# P1R4.net
KiCad netlist of a schematic drawn in EAGLE
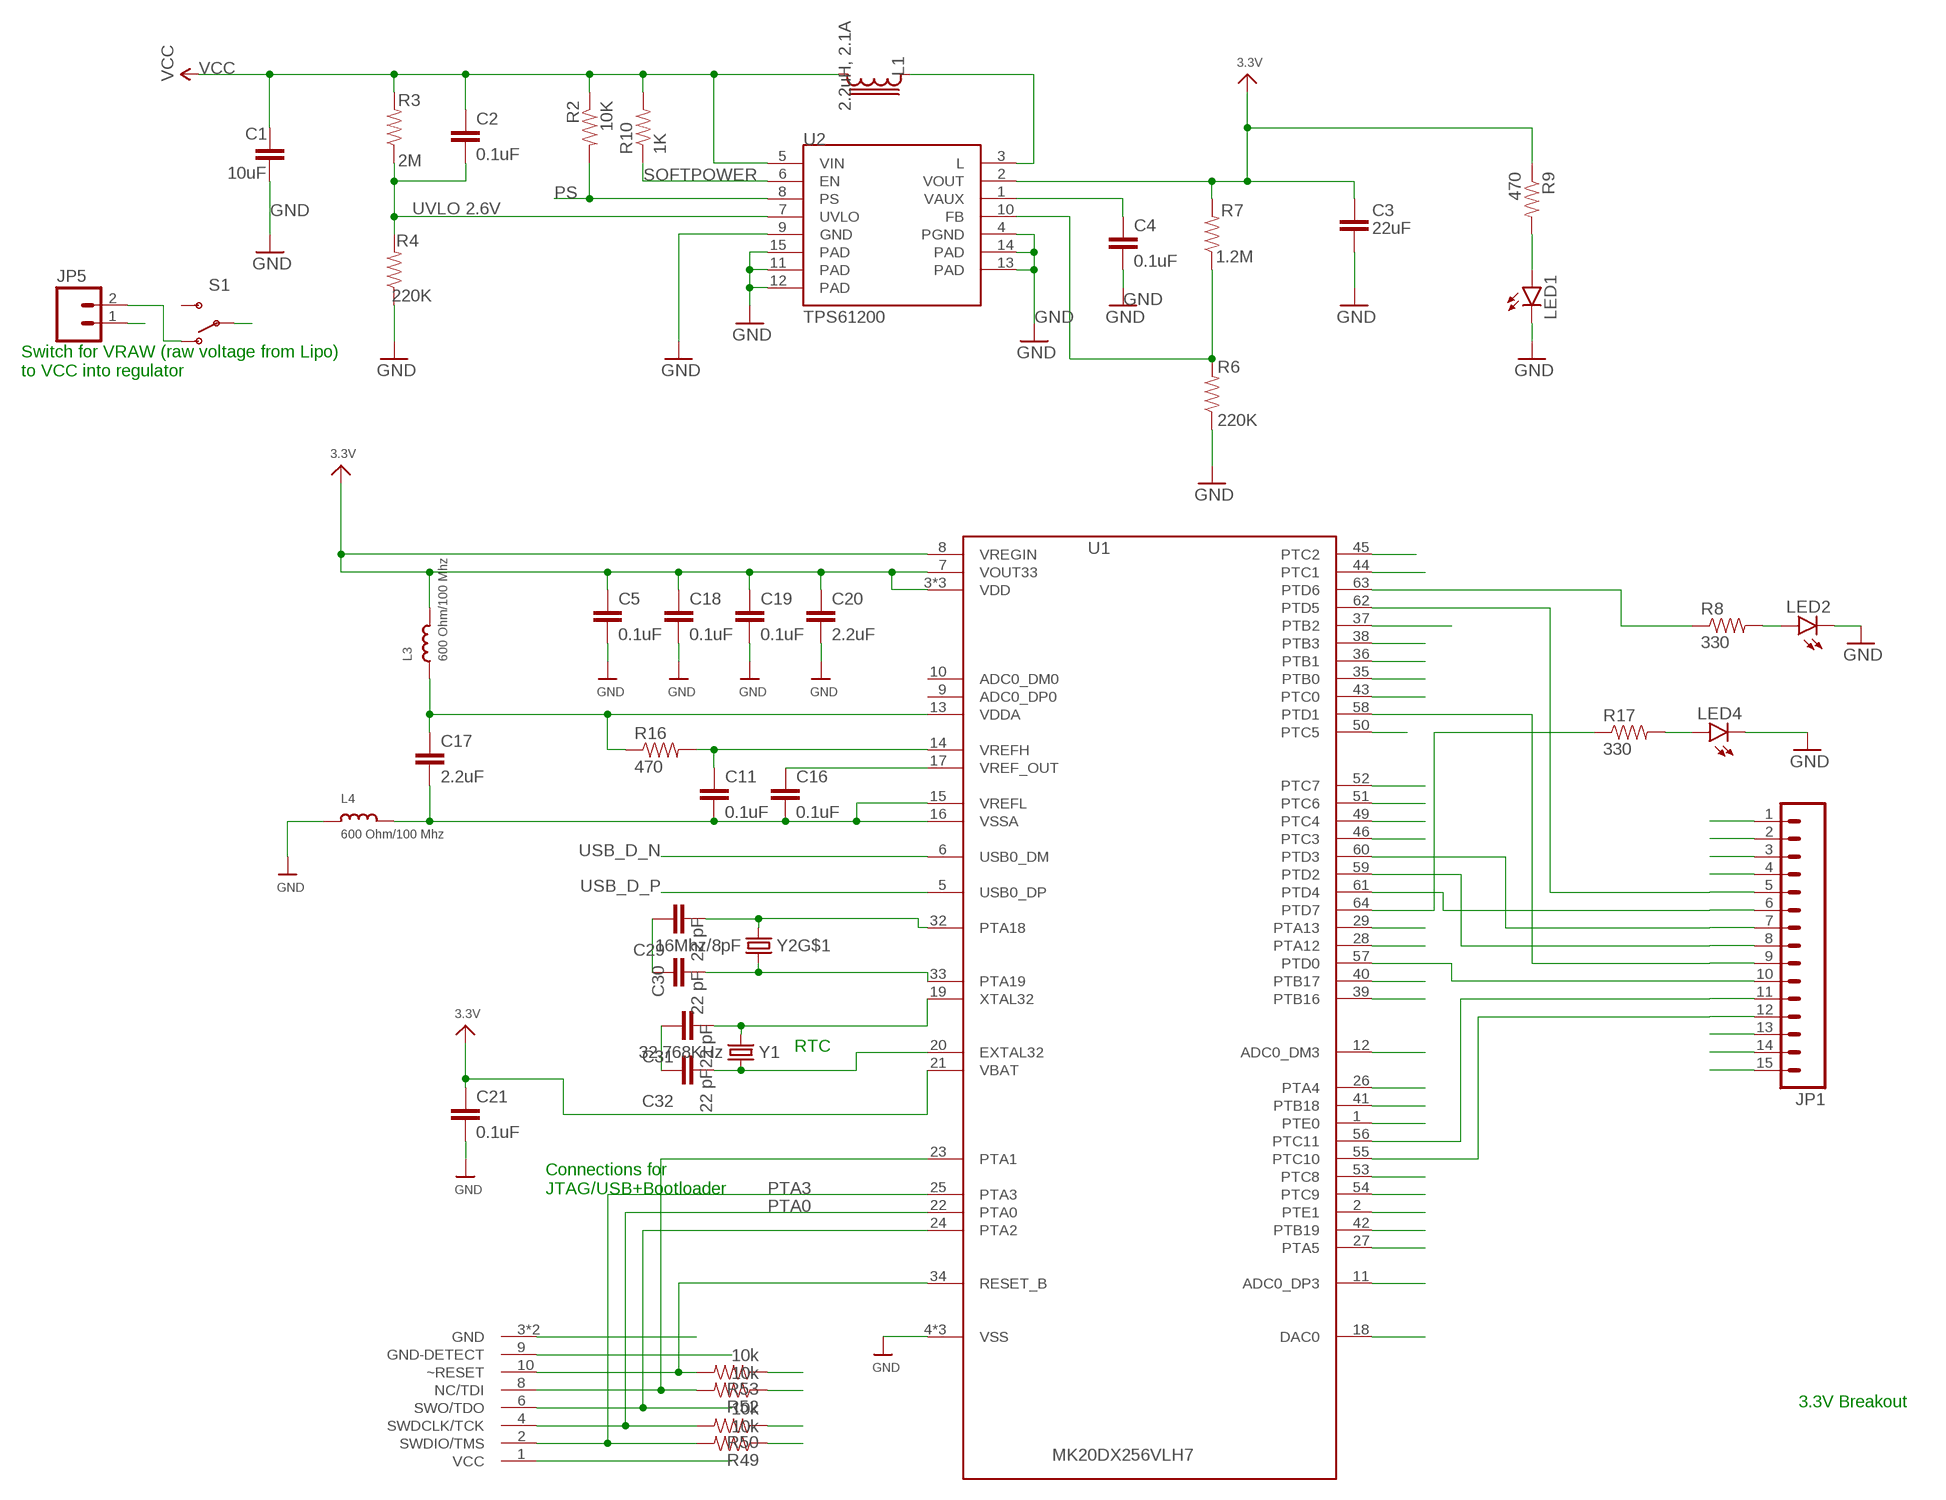
[diagram p0: schematic, sheet 1]
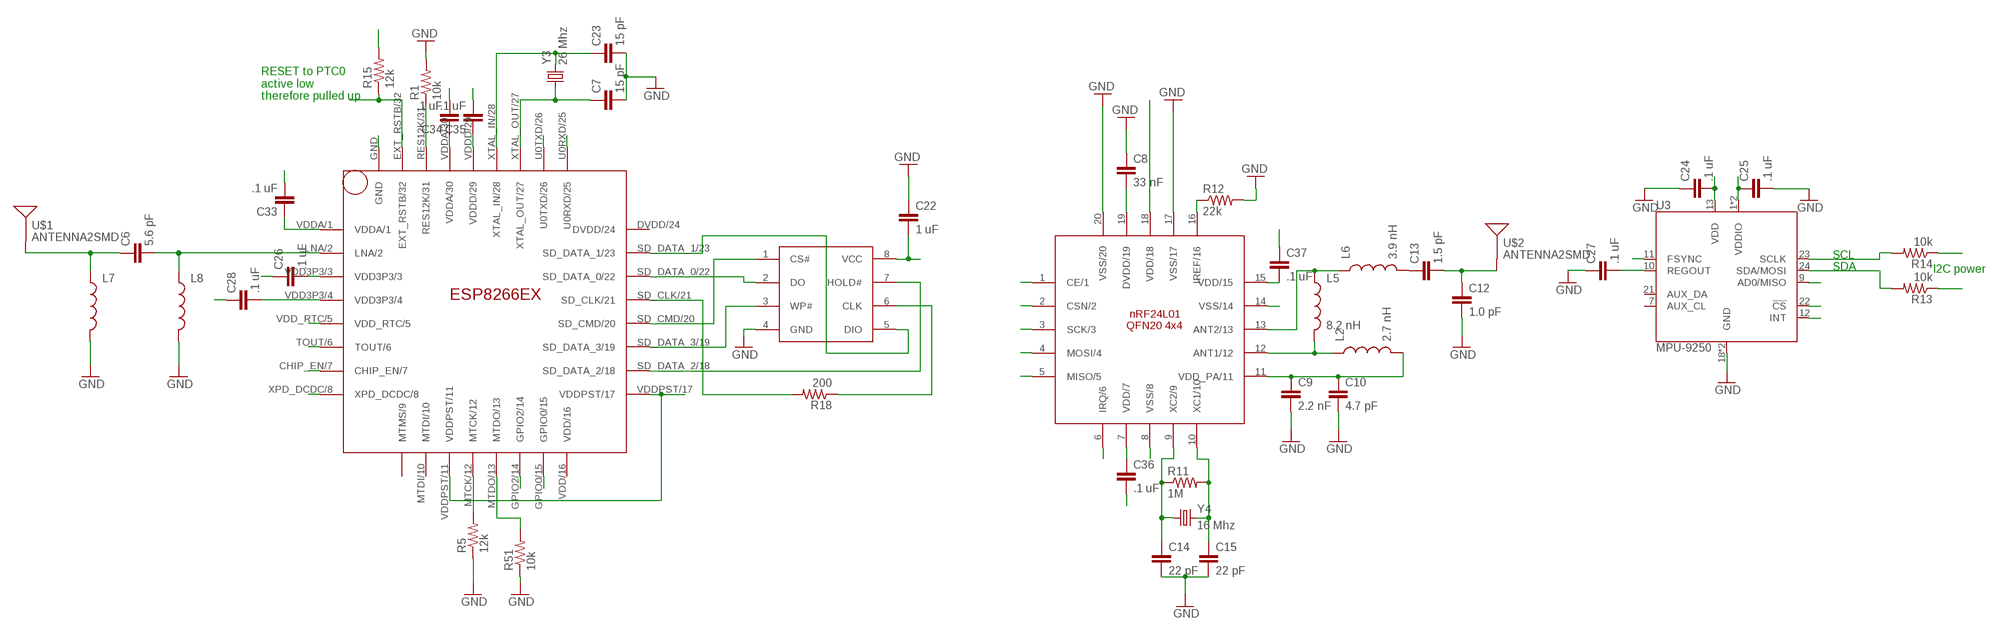
[diagram p1: schematic, sheet 2]
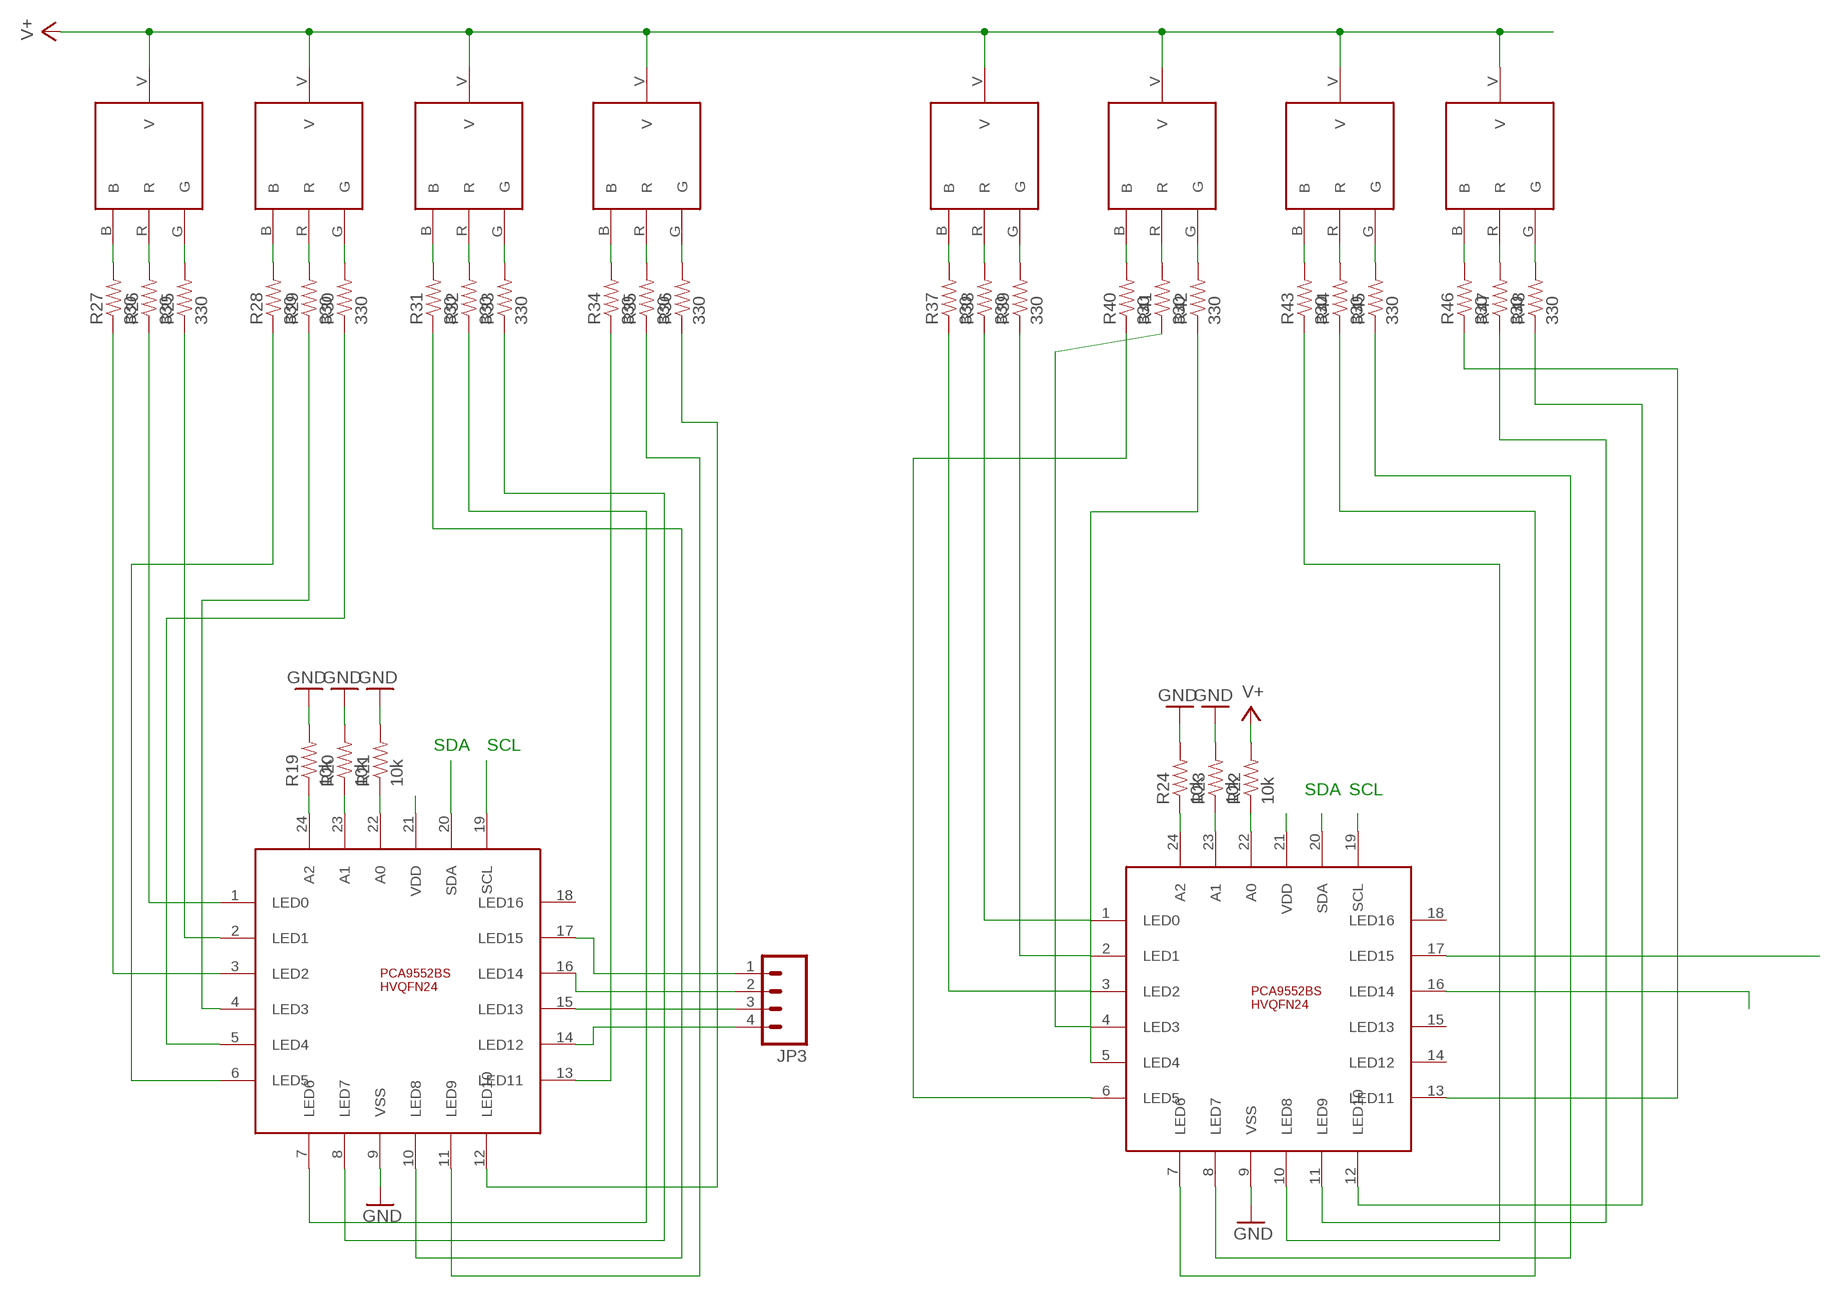
[diagram p2: schematic, sheet 3]

(export (version "E")
  (design (tool "Eeschema 10.0.6"))
  (components
    (comp (ref "JP3")
      (value "M04PTH")
      (footprint "eagle-import:1X04")
      (libsource (lib "eagle-import") (part "M04PTH"))
    )
    (comp (ref "R19")
      (value "10k")
      (footprint "eagle-import:0603-RES")
      (libsource (lib "eagle-import") (part "RESISTOR0603-RES"))
    )
    (comp (ref "R20")
      (value "10k")
      (footprint "eagle-import:0603-RES")
      (libsource (lib "eagle-import") (part "RESISTOR0603-RES"))
    )
    (comp (ref "R21")
      (value "10k")
      (footprint "eagle-import:0603-RES")
      (libsource (lib "eagle-import") (part "RESISTOR0603-RES"))
    )
    (comp (ref "R22")
      (value "10k")
      (footprint "eagle-import:0603-RES")
      (libsource (lib "eagle-import") (part "RESISTOR0603-RES"))
    )
    (comp (ref "R23")
      (value "10k")
      (footprint "eagle-import:0603-RES")
      (libsource (lib "eagle-import") (part "RESISTOR0603-RES"))
    )
    (comp (ref "R24")
      (value "10k")
      (footprint "eagle-import:0603-RES")
      (libsource (lib "eagle-import") (part "RESISTOR0603-RES"))
    )
    (comp (ref "R25")
      (value "330")
      (footprint "eagle-import:0402-RES")
      (libsource (lib "eagle-import") (part "RESISTOR0402-RES"))
    )
    (comp (ref "R26")
      (value "330")
      (footprint "eagle-import:0402-RES")
      (libsource (lib "eagle-import") (part "RESISTOR0402-RES"))
    )
    (comp (ref "R27")
      (value "330")
      (footprint "eagle-import:0402-RES")
      (libsource (lib "eagle-import") (part "RESISTOR0402-RES"))
    )
    (comp (ref "R28")
      (value "330")
      (footprint "eagle-import:0402-RES")
      (libsource (lib "eagle-import") (part "RESISTOR0402-RES"))
    )
    (comp (ref "R29")
      (value "330")
      (footprint "eagle-import:0402-RES")
      (libsource (lib "eagle-import") (part "RESISTOR0402-RES"))
    )
    (comp (ref "R30")
      (value "330")
      (footprint "eagle-import:0402-RES")
      (libsource (lib "eagle-import") (part "RESISTOR0402-RES"))
    )
    (comp (ref "R31")
      (value "330")
      (footprint "eagle-import:0402-RES")
      (libsource (lib "eagle-import") (part "RESISTOR0402-RES"))
    )
    (comp (ref "R32")
      (value "330")
      (footprint "eagle-import:0402-RES")
      (libsource (lib "eagle-import") (part "RESISTOR0402-RES"))
    )
    (comp (ref "R33")
      (value "330")
      (footprint "eagle-import:0402-RES")
      (libsource (lib "eagle-import") (part "RESISTOR0402-RES"))
    )
    (comp (ref "R34")
      (value "330")
      (footprint "eagle-import:0402-RES")
      (libsource (lib "eagle-import") (part "RESISTOR0402-RES"))
    )
    (comp (ref "R35")
      (value "330")
      (footprint "eagle-import:0402-RES")
      (libsource (lib "eagle-import") (part "RESISTOR0402-RES"))
    )
    (comp (ref "R36")
      (value "330")
      (footprint "eagle-import:0402-RES")
      (libsource (lib "eagle-import") (part "RESISTOR0402-RES"))
    )
    (comp (ref "R37")
      (value "330")
      (footprint "eagle-import:0402-RES")
      (libsource (lib "eagle-import") (part "RESISTOR0402-RES"))
    )
    (comp (ref "R38")
      (value "330")
      (footprint "eagle-import:0402-RES")
      (libsource (lib "eagle-import") (part "RESISTOR0402-RES"))
    )
    (comp (ref "R39")
      (value "330")
      (footprint "eagle-import:0402-RES")
      (libsource (lib "eagle-import") (part "RESISTOR0402-RES"))
    )
    (comp (ref "R40")
      (value "330")
      (footprint "eagle-import:0402-RES")
      (libsource (lib "eagle-import") (part "RESISTOR0402-RES"))
    )
    (comp (ref "R41")
      (value "330")
      (footprint "eagle-import:0402-RES")
      (libsource (lib "eagle-import") (part "RESISTOR0402-RES"))
    )
    (comp (ref "R42")
      (value "330")
      (footprint "eagle-import:0402-RES")
      (libsource (lib "eagle-import") (part "RESISTOR0402-RES"))
    )
    (comp (ref "R43")
      (value "330")
      (footprint "eagle-import:0402-RES")
      (libsource (lib "eagle-import") (part "RESISTOR0402-RES"))
    )
    (comp (ref "R44")
      (value "330")
      (footprint "eagle-import:0402-RES")
      (libsource (lib "eagle-import") (part "RESISTOR0402-RES"))
    )
    (comp (ref "R45")
      (value "330")
      (footprint "eagle-import:0402-RES")
      (libsource (lib "eagle-import") (part "RESISTOR0402-RES"))
    )
    (comp (ref "R46")
      (value "330")
      (footprint "eagle-import:0402-RES")
      (libsource (lib "eagle-import") (part "RESISTOR0402-RES"))
    )
    (comp (ref "R47")
      (value "330")
      (footprint "eagle-import:0402-RES")
      (libsource (lib "eagle-import") (part "RESISTOR0402-RES"))
    )
    (comp (ref "R48")
      (value "330")
      (footprint "eagle-import:0402-RES")
      (libsource (lib "eagle-import") (part "RESISTOR0402-RES"))
    )
    (comp (ref "U$8")
      (value "LTST-C19FD1WT")
      (footprint "eagle-import:LTST-C19FD1WT")
      (libsource (lib "eagle-import") (part "LTST-C19FD1WT"))
    )
    (comp (ref "U$11")
      (value "LTST-C19FD1WT")
      (footprint "eagle-import:LTST-C19FD1WT")
      (libsource (lib "eagle-import") (part "LTST-C19FD1WT"))
    )
    (comp (ref "U$13")
      (value "LTST-C19FD1WT")
      (footprint "eagle-import:LTST-C19FD1WT")
      (libsource (lib "eagle-import") (part "LTST-C19FD1WT"))
    )
    (comp (ref "U$14")
      (value "LTST-C19FD1WT")
      (footprint "eagle-import:LTST-C19FD1WT")
      (libsource (lib "eagle-import") (part "LTST-C19FD1WT"))
    )
    (comp (ref "U$15")
      (value "LTST-C19FD1WT")
      (footprint "eagle-import:LTST-C19FD1WT")
      (libsource (lib "eagle-import") (part "LTST-C19FD1WT"))
    )
    (comp (ref "U$16")
      (value "LTST-C19FD1WT")
      (footprint "eagle-import:LTST-C19FD1WT")
      (libsource (lib "eagle-import") (part "LTST-C19FD1WT"))
    )
    (comp (ref "U$17")
      (value "LTST-C19FD1WT")
      (footprint "eagle-import:LTST-C19FD1WT")
      (libsource (lib "eagle-import") (part "LTST-C19FD1WT"))
    )
    (comp (ref "U$18")
      (value "LTST-C19FD1WT")
      (footprint "eagle-import:LTST-C19FD1WT")
      (libsource (lib "eagle-import") (part "LTST-C19FD1WT"))
    )
    (comp (ref "U$20")
      (value "PCA9552BS")
      (footprint "eagle-import:HVQFN24")
      (libsource (lib "eagle-import") (part "PCA9552BS"))
    )
    (comp (ref "U$21")
      (value "PCA9552BS")
      (footprint "eagle-import:HVQFN24")
      (libsource (lib "eagle-import") (part "PCA9552BS"))
    )
    (comp (ref "C1")
      (value "10uF")
      (footprint "eagle-import:0603-CAP")
      (fields (field (name "MF") "Murata") (field (name "MPN") "GRM188R60J106ME47D"))
      (libsource (lib "eagle-import") (part "CAPACITOR-10UF"))
    )
    (comp (ref "C2")
      (value "0.1uF")
      (footprint "eagle-import:0603-CAP")
      (fields (field (name "MF") "Kemet") (field (name "MPN") "C0603C104J3RACTU"))
      (libsource (lib "eagle-import") (part "CAPACITOR-0.1UF"))
    )
    (comp (ref "C3")
      (value "22uF")
      (footprint "eagle-import:0603-CAP")
      (fields (field (name "MF") "Murata") (field (name "MPN") "GRM188R60J226MEA0D"))
      (libsource (lib "eagle-import") (part "CAPACITOR-22UF"))
    )
    (comp (ref "C4")
      (value "0.1uF")
      (footprint "eagle-import:0603-CAP")
      (fields (field (name "MF") "Kemet") (field (name "MPN") "C0603C104J3RACTU"))
      (libsource (lib "eagle-import") (part "CAPACITOR-0.1UF"))
    )
    (comp (ref "C5")
      (value "0.1uF")
      (footprint "eagle-import:0603-CAP")
      (fields (field (name "MF") "Kemet") (field (name "MPN") "C0603C104J3RACTU"))
      (libsource (lib "eagle-import") (part "CAPACITOR-0.1UF"))
    )
    (comp (ref "C11")
      (value "0.1uF")
      (footprint "eagle-import:0603-CAP")
      (fields (field (name "MF") "Kemet") (field (name "MPN") "C0603C104J3RACTU"))
      (libsource (lib "eagle-import") (part "CAPACITOR-0.1UF"))
    )
    (comp (ref "C16")
      (value "0.1uF")
      (footprint "eagle-import:0603-CAP")
      (fields (field (name "MF") "Kemet") (field (name "MPN") "C0603C104J3RACTU"))
      (libsource (lib "eagle-import") (part "CAPACITOR-0.1UF"))
    )
    (comp (ref "C17")
      (value "2.2uF")
      (footprint "eagle-import:0603-CAP")
      (fields (field (name "MF") "Kemet") (field (name "MPN") "C0603C225K4PACTU"))
      (libsource (lib "eagle-import") (part "CAPACITOR-2.2UF"))
    )
    (comp (ref "C18")
      (value "0.1uF")
      (footprint "eagle-import:0603-CAP")
      (fields (field (name "MF") "Kemet") (field (name "MPN") "C0603C104J3RACTU"))
      (libsource (lib "eagle-import") (part "CAPACITOR-0.1UF"))
    )
    (comp (ref "C19")
      (value "0.1uF")
      (footprint "eagle-import:0603-CAP")
      (fields (field (name "MF") "Kemet") (field (name "MPN") "C0603C104J3RACTU"))
      (libsource (lib "eagle-import") (part "CAPACITOR-0.1UF"))
    )
    (comp (ref "C20")
      (value "2.2uF")
      (footprint "eagle-import:0603-CAP")
      (fields (field (name "MF") "Kemet") (field (name "MPN") "C0603C225K4PACTU"))
      (libsource (lib "eagle-import") (part "CAPACITOR-2.2UF"))
    )
    (comp (ref "C21")
      (value "0.1uF")
      (footprint "eagle-import:0603-CAP")
      (fields (field (name "MF") "Kemet") (field (name "MPN") "C0603C104J3RACTU"))
      (libsource (lib "eagle-import") (part "CAPACITOR-0.1UF"))
    )
    (comp (ref "C29")
      (value "22 pF")
      (footprint "eagle-import:0603-CAP")
      (fields (field (name "MF") "Murata") (field (name "MPN") "GRM188R60J106ME47D"))
      (libsource (lib "eagle-import") (part "CAPACITOR-10UF"))
    )
    (comp (ref "C30")
      (value "22 pF")
      (footprint "eagle-import:0603-CAP")
      (fields (field (name "MF") "Murata") (field (name "MPN") "GRM188R60J106ME47D"))
      (libsource (lib "eagle-import") (part "CAPACITOR-10UF"))
    )
    (comp (ref "C31")
      (value "22 pF")
      (footprint "eagle-import:0603-CAP")
      (fields (field (name "MF") "Murata") (field (name "MPN") "GRM188R60J106ME47D"))
      (libsource (lib "eagle-import") (part "CAPACITOR-10UF"))
    )
    (comp (ref "C32")
      (value "22 pF")
      (footprint "eagle-import:0603-CAP")
      (fields (field (name "MF") "Murata") (field (name "MPN") "GRM188R60J106ME47D"))
      (libsource (lib "eagle-import") (part "CAPACITOR-10UF"))
    )
    (comp (ref "JP1")
      (value "M15")
      (footprint "eagle-import:1X15")
      (libsource (lib "eagle-import") (part "M15"))
    )
    (comp (ref "JP5")
      (value "M02PTH")
      (footprint "eagle-import:1X02")
      (libsource (lib "eagle-import") (part "M02PTH"))
    )
    (comp (ref "L1")
      (value "2.2uH, 2.1A")
      (footprint "eagle-import:LPS3015")
      (fields (field (name "MF") "Coilcraft") (field (name "MPN") "LPS3015-222MRB"))
      (libsource (lib "eagle-import") (part "LPS30152.2UH"))
    )
    (comp (ref "L3")
      (value "600 Ohm/100 Mhz")
      (footprint "eagle-import:0805")
      (fields (field (name "MF") "Taiyo Yuden") (field (name "MPN") "BK2125HM601-T"))
      (libsource (lib "eagle-import") (part "INDUCTOR-BK2125HM601-T"))
    )
    (comp (ref "L4")
      (value "600 Ohm/100 Mhz")
      (footprint "eagle-import:0805")
      (fields (field (name "MF") "Taiyo Yuden") (field (name "MPN") "BK2125HM601-T"))
      (libsource (lib "eagle-import") (part "INDUCTOR-BK2125HM601-T"))
    )
    (comp (ref "LED1")
      (value "LED-GREEN")
      (footprint "eagle-import:LED-0603")
      (fields (field (name "MF") "Avago") (field (name "MPN") "HSMG-C190"))
      (libsource (lib "eagle-import") (part "LED-GREEN"))
    )
    (comp (ref "LED2")
      (value "LED-GREEN")
      (footprint "eagle-import:LED-0603")
      (fields (field (name "MF") "Avago") (field (name "MPN") "HSMG-C190"))
      (libsource (lib "eagle-import") (part "LED-GREEN"))
    )
    (comp (ref "LED4")
      (value "LED-GREEN")
      (footprint "eagle-import:LED-0603")
      (fields (field (name "MF") "Avago") (field (name "MPN") "HSMG-C190"))
      (libsource (lib "eagle-import") (part "LED-GREEN"))
    )
    (comp (ref "R2")
      (value "10K")
      (footprint "eagle-import:0603-RES")
      (fields (field (name "MF") "Panasonic") (field (name "MPN") "ERJ-3GEYJ103V"))
      (libsource (lib "eagle-import") (part "RESISTOR-10K"))
    )
    (comp (ref "R3")
      (value "2M")
      (footprint "eagle-import:0603-RES")
      (fields (field (name "MF") "Panasonic") (field (name "MPN") "ERJ-3GEYJ205V"))
      (libsource (lib "eagle-import") (part "RESISTOR-2M"))
    )
    (comp (ref "R4")
      (value "220K")
      (footprint "eagle-import:0603-RES")
      (fields (field (name "MF") "Panasonic") (field (name "MPN") "ERJ-3GEYJ224V"))
      (libsource (lib "eagle-import") (part "RESISTOR-220K"))
    )
    (comp (ref "R6")
      (value "220K")
      (footprint "eagle-import:0603-RES")
      (fields (field (name "MF") "Panasonic") (field (name "MPN") "ERJ-3GEYJ224V"))
      (libsource (lib "eagle-import") (part "RESISTOR-220K"))
    )
    (comp (ref "R7")
      (value "1.2M")
      (footprint "eagle-import:0603-RES")
      (fields (field (name "MF") "Panasonic") (field (name "MPN") "ERJ-3GEYJ125V"))
      (libsource (lib "eagle-import") (part "RESISTOR-1.2M"))
    )
    (comp (ref "R8")
      (value "330")
      (footprint "eagle-import:0603-RES")
      (fields (field (name "MF") "Panasonic") (field (name "MPN") "ERJ-3GEYJ471V"))
      (libsource (lib "eagle-import") (part "RESISTOR-470"))
    )
    (comp (ref "R9")
      (value "470")
      (footprint "eagle-import:0603-RES")
      (fields (field (name "MF") "Panasonic") (field (name "MPN") "ERJ-3GEYJ471V"))
      (libsource (lib "eagle-import") (part "RESISTOR-470"))
    )
    (comp (ref "R10")
      (value "1K")
      (footprint "eagle-import:0603-RES")
      (fields (field (name "MF") "Panasonic") (field (name "MPN") "ERJ-3GEYJ102V"))
      (libsource (lib "eagle-import") (part "RESISTOR-1K"))
    )
    (comp (ref "R16")
      (value "470")
      (footprint "eagle-import:0603-RES")
      (fields (field (name "MF") "Panasonic") (field (name "MPN") "ERJ-3GEYJ471V"))
      (libsource (lib "eagle-import") (part "RESISTOR-470"))
    )
    (comp (ref "R17")
      (value "330")
      (footprint "eagle-import:0603-RES")
      (fields (field (name "MF") "Panasonic") (field (name "MPN") "ERJ-3GEYJ471V"))
      (libsource (lib "eagle-import") (part "RESISTOR-470"))
    )
    (comp (ref "R49")
      (value "10k")
      (footprint "eagle-import:0402-RES")
      (libsource (lib "eagle-import") (part "RESISTOR0402-RES"))
    )
    (comp (ref "R50")
      (value "10k")
      (footprint "eagle-import:0402-RES")
      (libsource (lib "eagle-import") (part "RESISTOR0402-RES"))
    )
    (comp (ref "R52")
      (value "10k")
      (footprint "eagle-import:0402-RES")
      (libsource (lib "eagle-import") (part "RESISTOR0402-RES"))
    )
    (comp (ref "R53")
      (value "10k")
      (footprint "eagle-import:0402-RES")
      (libsource (lib "eagle-import") (part "RESISTOR0402-RES"))
    )
    (comp (ref "S1")
      (value "SWITCH-SPDT-SMD-A")
      (footprint "eagle-import:SWITCH-SPST-SMD-A")
      (libsource (lib "eagle-import") (part "SWITCH-SPDT-SMD-A"))
    )
    (comp (ref "U$7")
      (value "2X5_0.05\"_CORTEX_DEBUGTH_NOKEY_UNSHROUDED")
      (footprint "eagle-import:2X5_0.05__TH_NS")
      (libsource (lib "eagle-import") (part "2X5_0.05{dblquote}_CORTEX_DEBUGTH_NOKEY_UNSHROUDED"))
    )
    (comp (ref "U1")
      (value "MK20DX256VLH7")
      (footprint "eagle-import:MK20DX256VLH7")
      (fields (field (name "MF") "Freescale"))
      (libsource (lib "eagle-import") (part "MK20DX256VLH7"))
    )
    (comp (ref "U2")
      (value "TPS61200")
      (footprint "eagle-import:QFN-10_PAD")
      (fields (field (name "MF") "Texas Instruments") (field (name "MPN") "TPS61200DRCR"))
      (libsource (lib "eagle-import") (part "TPS61200"))
    )
    (comp (ref "Y1")
      (value "32.768KHz")
      (footprint "eagle-import:CRYSTAL-TXC-7A")
      (fields (field (name "MF") "Epson Timing") (field (name "MPN") "FC-255 32.7680K-A3"))
      (libsource (lib "eagle-import") (part "CRYSTAL/32.768KHZ/SMD-TXC_7A"))
    )
    (comp (ref "Y2")
      (value "16Mhz/8pF")
      (footprint "eagle-import:CRYSTAL-SMD-5X3")
      (fields (field (name "MF") "ECS") (field (name "MPN") "ECS-160-8-30B-CKM"))
      (libsource (lib "eagle-import") (part "CRYSTAL/SMD-5X3-GND16MHZ/8PF"))
    )
    (comp (ref "C6")
      (value "5.6 pF")
      (footprint "eagle-import:0603-CAP")
      (libsource (lib "eagle-import") (part "CAP0603-CAP"))
    )
    (comp (ref "C7")
      (value "15 pF")
      (footprint "eagle-import:0603-CAP")
      (libsource (lib "eagle-import") (part "CAP0603-CAP"))
    )
    (comp (ref "C8")
      (value "33 nF")
      (footprint "eagle-import:0603-CAP")
      (libsource (lib "eagle-import") (part "CAP0603-CAP"))
    )
    (comp (ref "C9")
      (value "2.2 nF")
      (footprint "eagle-import:0603-CAP")
      (libsource (lib "eagle-import") (part "CAP0603-CAP"))
    )
    (comp (ref "C10")
      (value "4.7 pF")
      (footprint "eagle-import:0603-CAP")
      (libsource (lib "eagle-import") (part "CAP0603-CAP"))
    )
    (comp (ref "C12")
      (value "1.0 pF")
      (footprint "eagle-import:0603-CAP")
      (libsource (lib "eagle-import") (part "CAP0603-CAP"))
    )
    (comp (ref "C13")
      (value "1.5 pF")
      (footprint "eagle-import:0603-CAP")
      (libsource (lib "eagle-import") (part "CAP0603-CAP"))
    )
    (comp (ref "C14")
      (value "22 pF")
      (footprint "eagle-import:0603-CAP")
      (libsource (lib "eagle-import") (part "CAP0603-CAP"))
    )
    (comp (ref "C15")
      (value "22 pF")
      (footprint "eagle-import:0603-CAP")
      (libsource (lib "eagle-import") (part "CAP0603-CAP"))
    )
    (comp (ref "C22")
      (value "1 uF")
      (footprint "eagle-import:0603-CAP")
      (libsource (lib "eagle-import") (part "CAP0603-CAP"))
    )
    (comp (ref "C23")
      (value "15 pF")
      (footprint "eagle-import:0603-CAP")
      (libsource (lib "eagle-import") (part "CAP0603-CAP"))
    )
    (comp (ref "C24")
      (value ".1 uF")
      (footprint "eagle-import:0603-CAP")
      (libsource (lib "eagle-import") (part "CAP0603-CAP"))
    )
    (comp (ref "C25")
      (value ".1 uF")
      (footprint "eagle-import:0603-CAP")
      (libsource (lib "eagle-import") (part "CAP0603-CAP"))
    )
    (comp (ref "C26")
      (value ".1 uF")
      (footprint "eagle-import:0603-CAP")
      (libsource (lib "eagle-import") (part "CAP0603-CAP"))
    )
    (comp (ref "C27")
      (value ".1 uF")
      (footprint "eagle-import:0603-CAP")
      (libsource (lib "eagle-import") (part "CAP0603-CAP"))
    )
    (comp (ref "C28")
      (value ".1 uF")
      (footprint "eagle-import:0603-CAP")
      (libsource (lib "eagle-import") (part "CAP0603-CAP"))
    )
    (comp (ref "C33")
      (value ".1 uF")
      (footprint "eagle-import:0603-CAP")
      (libsource (lib "eagle-import") (part "CAP0603-CAP"))
    )
    (comp (ref "C34")
      (value ".1 uF")
      (footprint "eagle-import:0603-CAP")
      (libsource (lib "eagle-import") (part "CAP0603-CAP"))
    )
    (comp (ref "C35")
      (value ".1 uF")
      (footprint "eagle-import:0603-CAP")
      (libsource (lib "eagle-import") (part "CAP0603-CAP"))
    )
    (comp (ref "C36")
      (value ".1 uF")
      (footprint "eagle-import:0603-CAP")
      (libsource (lib "eagle-import") (part "CAP0603-CAP"))
    )
    (comp (ref "C37")
      (value ".1 uF")
      (footprint "eagle-import:0603-CAP")
      (libsource (lib "eagle-import") (part "CAP0603-CAP"))
    )
    (comp (ref "L2")
      (value "2.7 nH")
      (footprint "eagle-import:C0402")
      (libsource (lib "eagle-import") (part "INDUCTOR0402"))
    )
    (comp (ref "L5")
      (value "8.2 nH")
      (footprint "eagle-import:C0402")
      (libsource (lib "eagle-import") (part "INDUCTOR0402"))
    )
    (comp (ref "L6")
      (value "3.9 nH")
      (footprint "eagle-import:C0402")
      (libsource (lib "eagle-import") (part "INDUCTOR0402"))
    )
    (comp (ref "L7")
      (value "INDUCTOR30OHM,1.8A")
      (footprint "eagle-import:0603")
      (libsource (lib "eagle-import") (part "INDUCTOR30OHM,1.8A"))
    )
    (comp (ref "L8")
      (value "INDUCTOR30OHM,1.8A")
      (footprint "eagle-import:0603")
      (libsource (lib "eagle-import") (part "INDUCTOR30OHM,1.8A"))
    )
    (comp (ref "R1")
      (value "10k")
      (footprint "eagle-import:0603-RES")
      (libsource (lib "eagle-import") (part "SparkFun-Resistors_RESISTOR0603-RES"))
    )
    (comp (ref "R5")
      (value "12k")
      (footprint "eagle-import:0603-RES")
      (libsource (lib "eagle-import") (part "SparkFun-Resistors_RESISTOR0603-RES"))
    )
    (comp (ref "R11")
      (value "1M")
      (footprint "eagle-import:0603-RES")
      (libsource (lib "eagle-import") (part "SparkFun-Resistors_RESISTOR0603-RES"))
    )
    (comp (ref "R12")
      (value "22k")
      (footprint "eagle-import:0603-RES")
      (libsource (lib "eagle-import") (part "SparkFun-Resistors_RESISTOR0603-RES"))
    )
    (comp (ref "R13")
      (value "10k")
      (footprint "eagle-import:0603-RES")
      (libsource (lib "eagle-import") (part "SparkFun-Resistors_RESISTOR0603-RES"))
    )
    (comp (ref "R14")
      (value "10k")
      (footprint "eagle-import:0603-RES")
      (libsource (lib "eagle-import") (part "SparkFun-Resistors_RESISTOR0603-RES"))
    )
    (comp (ref "R15")
      (value "12k")
      (footprint "eagle-import:0603-RES")
      (libsource (lib "eagle-import") (part "SparkFun-Resistors_RESISTOR0603-RES"))
    )
    (comp (ref "R18")
      (value "200")
      (footprint "eagle-import:0603-RES")
      (libsource (lib "eagle-import") (part "SparkFun-Resistors_RESISTOR0603-RES"))
    )
    (comp (ref "R51")
      (value "10k")
      (footprint "eagle-import:0603-RES")
      (libsource (lib "eagle-import") (part "SparkFun-Resistors_RESISTOR0603-RES"))
    )
    (comp (ref "U$1")
      (value "ANTENNA2SMD")
      (footprint "eagle-import:ANTENNA-CHIP2")
      (libsource (lib "eagle-import") (part "ANTENNA2SMD"))
    )
    (comp (ref "U$2")
      (value "ANTENNA2SMD")
      (footprint "eagle-import:ANTENNA-CHIP2")
      (libsource (lib "eagle-import") (part "ANTENNA2SMD"))
    )
    (comp (ref "U$3")
      (value "25Q40")
      (footprint "eagle-import:SOP8")
      (libsource (lib "eagle-import") (part "25Q40"))
    )
    (comp (ref "U$4")
      (value "NRF24L01")
      (footprint "eagle-import:QFN20(4X4)")
      (libsource (lib "eagle-import") (part "NRF24L01"))
    )
    (comp (ref "U$6")
      (value "ESP8266EX")
      (footprint "eagle-import:QFN32")
      (libsource (lib "eagle-import") (part "ESP8266EX"))
    )
    (comp (ref "U3")
      (value "MPU-9250")
      (footprint "eagle-import:QFN-24_3MM")
      (libsource (lib "eagle-import") (part "MPU-9250"))
    )
    (comp (ref "Y3")
      (value "26 Mhz")
      (footprint "eagle-import:CRYSTAL-SMD-5X3")
      (libsource (lib "eagle-import") (part "CRYSTAL5X3"))
    )
    (comp (ref "Y4")
      (value "16 Mhz")
      (footprint "eagle-import:CRYSTAL-SMD-5X3")
      (libsource (lib "eagle-import") (part "CRYSTAL5X3"))
    )
  )
  (nets
    (net (code "1") (name "3.3V") (class "Default")
      (node (ref "C18") (pin "1") (pinfunction "1_1") (pintype "passive"))
      (node (ref "C19") (pin "1") (pinfunction "1_1") (pintype "passive"))
      (node (ref "C20") (pin "1") (pinfunction "1_1") (pintype "passive"))
      (node (ref "C21") (pin "1") (pinfunction "1_1") (pintype "passive"))
      (node (ref "C22") (pin "2") (pinfunction "2_2") (pintype "passive"))
      (node (ref "C24") (pin "2") (pinfunction "2_2") (pintype "passive"))
      (node (ref "C25") (pin "1") (pinfunction "1_1") (pintype "passive"))
      (node (ref "C26") (pin "2") (pinfunction "2_2") (pintype "passive"))
      (node (ref "C28") (pin "2") (pinfunction "2_2") (pintype "passive"))
      (node (ref "C3") (pin "1") (pinfunction "1_1") (pintype "passive"))
      (node (ref "C33") (pin "1") (pinfunction "1_1") (pintype "passive"))
      (node (ref "C34") (pin "1") (pinfunction "1_1") (pintype "passive"))
      (node (ref "C35") (pin "1") (pinfunction "1_1") (pintype "passive"))
      (node (ref "C36") (pin "1") (pinfunction "1_1") (pintype "passive"))
      (node (ref "C37") (pin "2") (pinfunction "2_2") (pintype "passive"))
      (node (ref "C5") (pin "1") (pinfunction "1_1") (pintype "passive"))
      (node (ref "JP1") (pin "13") (pinfunction "13_13") (pintype "passive"))
      (node (ref "JP1") (pin "14") (pinfunction "14_14") (pintype "passive"))
      (node (ref "JP1") (pin "15") (pinfunction "15_15") (pintype "passive"))
      (node (ref "L3") (pin "2") (pinfunction "2_2") (pintype "passive"))
      (node (ref "R13") (pin "1") (pinfunction "1_1") (pintype "passive"))
      (node (ref "R14") (pin "1") (pinfunction "1_1") (pintype "passive"))
      (node (ref "R15") (pin "2") (pinfunction "2_2") (pintype "passive"))
      (node (ref "R22") (pin "2") (pinfunction "2_2") (pintype "passive"))
      (node (ref "R49") (pin "1") (pinfunction "1_1") (pintype "passive"))
      (node (ref "R52") (pin "1") (pinfunction "1_1") (pintype "passive"))
      (node (ref "R53") (pin "1") (pinfunction "1_1") (pintype "passive"))
      (node (ref "R7") (pin "2") (pinfunction "2_2") (pintype "passive"))
      (node (ref "R9") (pin "1") (pinfunction "1_1") (pintype "passive"))
      (node (ref "U$11") (pin "V") (pinfunction "V_V") (pintype "bidirectional"))
      (node (ref "U$13") (pin "V") (pinfunction "V_V") (pintype "bidirectional"))
      (node (ref "U$14") (pin "V") (pinfunction "V_V") (pintype "bidirectional"))
      (node (ref "U$15") (pin "V") (pinfunction "V_V") (pintype "bidirectional"))
      (node (ref "U$16") (pin "V") (pinfunction "V_V") (pintype "bidirectional"))
      (node (ref "U$17") (pin "V") (pinfunction "V_V") (pintype "bidirectional"))
      (node (ref "U$18") (pin "V") (pinfunction "V_V") (pintype "bidirectional"))
      (node (ref "U$20") (pin "21") (pinfunction "VDD_21") (pintype "bidirectional"))
      (node (ref "U$21") (pin "21") (pinfunction "VDD_21") (pintype "bidirectional"))
      (node (ref "U$3") (pin "8") (pinfunction "VCC_8") (pintype "bidirectional"))
      (node (ref "U$4") (pin "15") (pinfunction "VDD/15_15") (pintype "bidirectional"))
      (node (ref "U$4") (pin "18") (pinfunction "VDD/18_18") (pintype "bidirectional"))
      (node (ref "U$4") (pin "7") (pinfunction "VDD/7_7") (pintype "bidirectional"))
      (node (ref "U$6") (pin "VDD3P3/3") (pinfunction "VDD3P3/3_VDD3P3/3") (pintype "bidirectional"))
      (node (ref "U$6") (pin "VDD3P3/4") (pinfunction "VDD3P3/4_VDD3P3/4") (pintype "bidirectional"))
      (node (ref "U$6") (pin "VDDA/1") (pinfunction "VDDA/1_VDDA/1") (pintype "bidirectional"))
      (node (ref "U$6") (pin "VDDA/30") (pinfunction "VDDA/30_VDDA/30") (pintype "bidirectional"))
      (node (ref "U$6") (pin "VDDD/29") (pinfunction "VDDD/29_VDDD/29") (pintype "bidirectional"))
      (node (ref "U$6") (pin "VDDPST/11") (pinfunction "VDDPST/11_VDDPST/11") (pintype "bidirectional"))
      (node (ref "U$6") (pin "VDDPST/17") (pinfunction "VDDPST/17_VDDPST/17") (pintype "bidirectional"))
      (node (ref "U$7") (pin "1") (pinfunction "VCC_1") (pintype "bidirectional"))
      (node (ref "U$8") (pin "V") (pinfunction "V_V") (pintype "bidirectional"))
      (node (ref "U1") (pin "21") (pinfunction "VBAT_21") (pintype "bidirectional"))
      (node (ref "U1") (pin "3") (pinfunction "VDD_3") (pintype "bidirectional"))
      (node (ref "U1") (pin "30") (pinfunction "VDD_30") (pintype "bidirectional"))
      (node (ref "U1") (pin "48") (pinfunction "VDD_48") (pintype "bidirectional"))
      (node (ref "U1") (pin "7") (pinfunction "VOUT33_7") (pintype "bidirectional"))
      (node (ref "U1") (pin "8") (pinfunction "VREGIN_8") (pintype "bidirectional"))
      (node (ref "U2") (pin "2") (pinfunction "VOUT_2") (pintype "passive"))
      (node (ref "U3") (pin "1") (pinfunction "VDDIO_1") (pintype "bidirectional"))
      (node (ref "U3") (pin "13") (pinfunction "VDD_13") (pintype "bidirectional"))
      (node (ref "U3") (pin "22") (pinfunction "~{CS}_22") (pintype "bidirectional"))
      (node (ref "U3") (pin "8") (pinfunction "VDDIO_8") (pintype "bidirectional"))
    )
    (net (code "2") (name "AD0") (class "Default")
      (node (ref "U1") (pin "45") (pinfunction "PTC2_45") (pintype "bidirectional"))
      (node (ref "U3") (pin "9") (pinfunction "AD0/MISO_9") (pintype "bidirectional"))
    )
    (net (code "3") (name "GND") (class "Default")
      (node (ref "C1") (pin "2") (pinfunction "2_2") (pintype "passive"))
      (node (ref "C10") (pin "2") (pinfunction "2_2") (pintype "passive"))
      (node (ref "C12") (pin "2") (pinfunction "2_2") (pintype "passive"))
      (node (ref "C14") (pin "2") (pinfunction "2_2") (pintype "passive"))
      (node (ref "C15") (pin "2") (pinfunction "2_2") (pintype "passive"))
      (node (ref "C18") (pin "2") (pinfunction "2_2") (pintype "passive"))
      (node (ref "C19") (pin "2") (pinfunction "2_2") (pintype "passive"))
      (node (ref "C20") (pin "2") (pinfunction "2_2") (pintype "passive"))
      (node (ref "C21") (pin "2") (pinfunction "2_2") (pintype "passive"))
      (node (ref "C22") (pin "1") (pinfunction "1_1") (pintype "passive"))
      (node (ref "C23") (pin "2") (pinfunction "2_2") (pintype "passive"))
      (node (ref "C24") (pin "1") (pinfunction "1_1") (pintype "passive"))
      (node (ref "C25") (pin "2") (pinfunction "2_2") (pintype "passive"))
      (node (ref "C26") (pin "1") (pinfunction "1_1") (pintype "passive"))
      (node (ref "C27") (pin "1") (pinfunction "1_1") (pintype "passive"))
      (node (ref "C28") (pin "1") (pinfunction "1_1") (pintype "passive"))
      (node (ref "C29") (pin "1") (pinfunction "1_1") (pintype "passive"))
      (node (ref "C3") (pin "2") (pinfunction "2_2") (pintype "passive"))
      (node (ref "C30") (pin "1") (pinfunction "1_1") (pintype "passive"))
      (node (ref "C31") (pin "1") (pinfunction "1_1") (pintype "passive"))
      (node (ref "C32") (pin "1") (pinfunction "1_1") (pintype "passive"))
      (node (ref "C33") (pin "2") (pinfunction "2_2") (pintype "passive"))
      (node (ref "C34") (pin "2") (pinfunction "2_2") (pintype "passive"))
      (node (ref "C35") (pin "2") (pinfunction "2_2") (pintype "passive"))
      (node (ref "C36") (pin "2") (pinfunction "2_2") (pintype "passive"))
      (node (ref "C37") (pin "1") (pinfunction "1_1") (pintype "passive"))
      (node (ref "C4") (pin "2") (pinfunction "2_2") (pintype "passive"))
      (node (ref "C5") (pin "2") (pinfunction "2_2") (pintype "passive"))
      (node (ref "C7") (pin "2") (pinfunction "2_2") (pintype "passive"))
      (node (ref "C8") (pin "1") (pinfunction "1_1") (pintype "passive"))
      (node (ref "C9") (pin "2") (pinfunction "2_2") (pintype "passive"))
      (node (ref "JP1") (pin "1") (pinfunction "1_1") (pintype "passive"))
      (node (ref "JP1") (pin "2") (pinfunction "2_2") (pintype "passive"))
      (node (ref "JP1") (pin "3") (pinfunction "3_3") (pintype "passive"))
      (node (ref "JP1") (pin "4") (pinfunction "4_4") (pintype "passive"))
      (node (ref "JP5") (pin "1") (pinfunction "1_1") (pintype "passive"))
      (node (ref "L4") (pin "1") (pinfunction "1_1") (pintype "passive"))
      (node (ref "L7") (pin "2") (pinfunction "2_2") (pintype "passive"))
      (node (ref "L8") (pin "2") (pinfunction "2_2") (pintype "passive"))
      (node (ref "LED1") (pin "C") (pinfunction "C_C") (pintype "passive"))
      (node (ref "LED2") (pin "C") (pinfunction "C_C") (pintype "passive"))
      (node (ref "LED4") (pin "C") (pinfunction "C_C") (pintype "passive"))
      (node (ref "R1") (pin "2") (pinfunction "2_2") (pintype "passive"))
      (node (ref "R12") (pin "2") (pinfunction "2_2") (pintype "passive"))
      (node (ref "R19") (pin "2") (pinfunction "2_2") (pintype "passive"))
      (node (ref "R20") (pin "2") (pinfunction "2_2") (pintype "passive"))
      (node (ref "R21") (pin "2") (pinfunction "2_2") (pintype "passive"))
      (node (ref "R23") (pin "2") (pinfunction "2_2") (pintype "passive"))
      (node (ref "R24") (pin "2") (pinfunction "2_2") (pintype "passive"))
      (node (ref "R4") (pin "1") (pinfunction "1_1") (pintype "passive"))
      (node (ref "R5") (pin "1") (pinfunction "1_1") (pintype "passive"))
      (node (ref "R50") (pin "1") (pinfunction "1_1") (pintype "passive"))
      (node (ref "R51") (pin "1") (pinfunction "1_1") (pintype "passive"))
      (node (ref "R6") (pin "1") (pinfunction "1_1") (pintype "passive"))
      (node (ref "U$20") (pin "9") (pinfunction "VSS_9") (pintype "bidirectional"))
      (node (ref "U$21") (pin "9") (pinfunction "VSS_9") (pintype "bidirectional"))
      (node (ref "U$3") (pin "4") (pinfunction "GND_4") (pintype "bidirectional"))
      (node (ref "U$4") (pin "14") (pinfunction "VSS/14_14") (pintype "bidirectional"))
      (node (ref "U$4") (pin "17") (pinfunction "VSS/17_17") (pintype "bidirectional"))
      (node (ref "U$4") (pin "20") (pinfunction "VSS/20_20") (pintype "bidirectional"))
      (node (ref "U$4") (pin "8") (pinfunction "VSS/8_8") (pintype "bidirectional"))
      (node (ref "U$6") (pin "GND") (pinfunction "GND_GND") (pintype "bidirectional"))
      (node (ref "U$7") (pin "3") (pinfunction "GND_3") (pintype "bidirectional"))
      (node (ref "U$7") (pin "5") (pinfunction "GND_5") (pintype "bidirectional"))
      (node (ref "U$7") (pin "9") (pinfunction "GND-DETECT_9") (pintype "bidirectional"))
      (node (ref "U1") (pin "31") (pinfunction "VSS_31") (pintype "bidirectional"))
      (node (ref "U1") (pin "4") (pinfunction "VSS_4") (pintype "bidirectional"))
      (node (ref "U1") (pin "47") (pinfunction "VSS_47") (pintype "bidirectional"))
      (node (ref "U2") (pin "11") (pinfunction "PAD_11") (pintype "power_in"))
      (node (ref "U2") (pin "12") (pinfunction "PAD_12") (pintype "power_in"))
      (node (ref "U2") (pin "13") (pinfunction "PAD_13") (pintype "power_in"))
      (node (ref "U2") (pin "14") (pinfunction "PAD_14") (pintype "power_in"))
      (node (ref "U2") (pin "15") (pinfunction "PAD_15") (pintype "power_in"))
      (node (ref "U2") (pin "4") (pinfunction "PGND_4") (pintype "power_in"))
      (node (ref "U2") (pin "9") (pinfunction "GND_9") (pintype "power_in"))
      (node (ref "U3") (pin "18") (pinfunction "GND_18") (pintype "bidirectional"))
      (node (ref "U3") (pin "20") (pinfunction "GND_20") (pintype "bidirectional"))
    )
    (net (code "4") (name "Net-(C6-Pad2)") (class "Default")
      (node (ref "C6") (pin "2") (pinfunction "2_2") (pintype "passive"))
      (node (ref "L8") (pin "1") (pinfunction "1_1") (pintype "passive"))
      (node (ref "U$6") (pin "LNA/2") (pinfunction "LNA/2_LNA/2") (pintype "bidirectional"))
    )
    (net (code "5") (name "Net-(C7-Pad1)") (class "Default")
      (node (ref "C7") (pin "1") (pinfunction "1_1") (pintype "passive"))
      (node (ref "U$6") (pin "XTAL_OUT/27") (pinfunction "XTAL_OUT/27_XTAL_OUT/27") (pintype "bidirectional"))
      (node (ref "Y3") (pin "1") (pinfunction "1_1") (pintype "passive"))
    )
    (net (code "6") (name "Net-(C13-Pad1)") (class "Default")
      (node (ref "C13") (pin "1") (pinfunction "1_1") (pintype "passive"))
      (node (ref "L6") (pin "2") (pinfunction "2_2") (pintype "passive"))
    )
    (net (code "7") (name "Net-(LED1-PadA)") (class "Default")
      (node (ref "LED1") (pin "A") (pinfunction "A_A") (pintype "passive"))
      (node (ref "R9") (pin "2") (pinfunction "2_2") (pintype "passive"))
    )
    (net (code "8") (name "Net-(LED2-PadA)") (class "Default")
      (node (ref "LED2") (pin "A") (pinfunction "A_A") (pintype "passive"))
      (node (ref "R8") (pin "2") (pinfunction "2_2") (pintype "passive"))
    )
    (net (code "9") (name "Net-(LED4-PadA)") (class "Default")
      (node (ref "LED4") (pin "A") (pinfunction "A_A") (pintype "passive"))
      (node (ref "R17") (pin "2") (pinfunction "2_2") (pintype "passive"))
    )
    (net (code "10") (name "Net-(R1-Pad1)") (class "Default")
      (node (ref "R1") (pin "1") (pinfunction "1_1") (pintype "passive"))
      (node (ref "U$6") (pin "RES12K/31") (pinfunction "RES12K/31_RES12K/31") (pintype "bidirectional"))
    )
    (net (code "11") (name "Net-(R5-Pad2)") (class "Default")
      (node (ref "R5") (pin "2") (pinfunction "2_2") (pintype "passive"))
      (node (ref "U$6") (pin "MTCK/12") (pinfunction "MTCK/12_MTCK/12") (pintype "bidirectional"))
    )
    (net (code "12") (name "Net-(R18-Pad2)") (class "Default")
      (node (ref "R18") (pin "2") (pinfunction "2_2") (pintype "passive"))
      (node (ref "U$6") (pin "SD_CLK/21") (pinfunction "SD_CLK/21_SD_CLK/21") (pintype "bidirectional"))
    )
    (net (code "13") (name "Net-(R25-Pad2)") (class "Default")
      (node (ref "R25") (pin "2") (pinfunction "2_2") (pintype "passive"))
      (node (ref "U$8") (pin "G") (pinfunction "G_G") (pintype "bidirectional"))
    )
    (net (code "14") (name "Net-(R26-Pad2)") (class "Default")
      (node (ref "R26") (pin "2") (pinfunction "2_2") (pintype "passive"))
      (node (ref "U$8") (pin "R") (pinfunction "R_R") (pintype "bidirectional"))
    )
    (net (code "15") (name "Net-(R27-Pad2)") (class "Default")
      (node (ref "R27") (pin "2") (pinfunction "2_2") (pintype "passive"))
      (node (ref "U$8") (pin "B") (pinfunction "B_B") (pintype "bidirectional"))
    )
    (net (code "16") (name "Net-(R28-Pad2)") (class "Default")
      (node (ref "R28") (pin "2") (pinfunction "2_2") (pintype "passive"))
      (node (ref "U$11") (pin "B") (pinfunction "B_B") (pintype "bidirectional"))
    )
    (net (code "17") (name "Net-(R29-Pad2)") (class "Default")
      (node (ref "R29") (pin "2") (pinfunction "2_2") (pintype "passive"))
      (node (ref "U$11") (pin "R") (pinfunction "R_R") (pintype "bidirectional"))
    )
    (net (code "18") (name "Net-(R30-Pad2)") (class "Default")
      (node (ref "R30") (pin "2") (pinfunction "2_2") (pintype "passive"))
      (node (ref "U$11") (pin "G") (pinfunction "G_G") (pintype "bidirectional"))
    )
    (net (code "19") (name "Net-(R31-Pad2)") (class "Default")
      (node (ref "R31") (pin "2") (pinfunction "2_2") (pintype "passive"))
      (node (ref "U$13") (pin "B") (pinfunction "B_B") (pintype "bidirectional"))
    )
    (net (code "20") (name "Net-(R32-Pad2)") (class "Default")
      (node (ref "R32") (pin "2") (pinfunction "2_2") (pintype "passive"))
      (node (ref "U$13") (pin "R") (pinfunction "R_R") (pintype "bidirectional"))
    )
    (net (code "21") (name "Net-(R33-Pad2)") (class "Default")
      (node (ref "R33") (pin "2") (pinfunction "2_2") (pintype "passive"))
      (node (ref "U$13") (pin "G") (pinfunction "G_G") (pintype "bidirectional"))
    )
    (net (code "22") (name "Net-(R34-Pad2)") (class "Default")
      (node (ref "R34") (pin "2") (pinfunction "2_2") (pintype "passive"))
      (node (ref "U$14") (pin "B") (pinfunction "B_B") (pintype "bidirectional"))
    )
    (net (code "23") (name "Net-(R35-Pad2)") (class "Default")
      (node (ref "R35") (pin "2") (pinfunction "2_2") (pintype "passive"))
      (node (ref "U$14") (pin "R") (pinfunction "R_R") (pintype "bidirectional"))
    )
    (net (code "24") (name "Net-(R36-Pad2)") (class "Default")
      (node (ref "R36") (pin "2") (pinfunction "2_2") (pintype "passive"))
      (node (ref "U$14") (pin "G") (pinfunction "G_G") (pintype "bidirectional"))
    )
    (net (code "25") (name "Net-(R37-Pad2)") (class "Default")
      (node (ref "R37") (pin "2") (pinfunction "2_2") (pintype "passive"))
      (node (ref "U$15") (pin "B") (pinfunction "B_B") (pintype "bidirectional"))
    )
    (net (code "26") (name "Net-(R38-Pad2)") (class "Default")
      (node (ref "R38") (pin "2") (pinfunction "2_2") (pintype "passive"))
      (node (ref "U$15") (pin "R") (pinfunction "R_R") (pintype "bidirectional"))
    )
    (net (code "27") (name "Net-(R39-Pad2)") (class "Default")
      (node (ref "R39") (pin "2") (pinfunction "2_2") (pintype "passive"))
      (node (ref "U$15") (pin "G") (pinfunction "G_G") (pintype "bidirectional"))
    )
    (net (code "28") (name "Net-(R40-Pad2)") (class "Default")
      (node (ref "R40") (pin "2") (pinfunction "2_2") (pintype "passive"))
      (node (ref "U$16") (pin "B") (pinfunction "B_B") (pintype "bidirectional"))
    )
    (net (code "29") (name "Net-(R41-Pad2)") (class "Default")
      (node (ref "R41") (pin "2") (pinfunction "2_2") (pintype "passive"))
      (node (ref "U$16") (pin "R") (pinfunction "R_R") (pintype "bidirectional"))
    )
    (net (code "30") (name "Net-(R42-Pad2)") (class "Default")
      (node (ref "R42") (pin "2") (pinfunction "2_2") (pintype "passive"))
      (node (ref "U$16") (pin "G") (pinfunction "G_G") (pintype "bidirectional"))
    )
    (net (code "31") (name "Net-(R43-Pad2)") (class "Default")
      (node (ref "R43") (pin "2") (pinfunction "2_2") (pintype "passive"))
      (node (ref "U$17") (pin "B") (pinfunction "B_B") (pintype "bidirectional"))
    )
    (net (code "32") (name "Net-(R44-Pad2)") (class "Default")
      (node (ref "R44") (pin "2") (pinfunction "2_2") (pintype "passive"))
      (node (ref "U$17") (pin "R") (pinfunction "R_R") (pintype "bidirectional"))
    )
    (net (code "33") (name "Net-(R45-Pad2)") (class "Default")
      (node (ref "R45") (pin "2") (pinfunction "2_2") (pintype "passive"))
      (node (ref "U$17") (pin "G") (pinfunction "G_G") (pintype "bidirectional"))
    )
    (net (code "34") (name "Net-(R46-Pad2)") (class "Default")
      (node (ref "R46") (pin "2") (pinfunction "2_2") (pintype "passive"))
      (node (ref "U$18") (pin "B") (pinfunction "B_B") (pintype "bidirectional"))
    )
    (net (code "35") (name "Net-(R47-Pad2)") (class "Default")
      (node (ref "R47") (pin "2") (pinfunction "2_2") (pintype "passive"))
      (node (ref "U$18") (pin "R") (pinfunction "R_R") (pintype "bidirectional"))
    )
    (net (code "36") (name "Net-(R48-Pad2)") (class "Default")
      (node (ref "R48") (pin "2") (pinfunction "2_2") (pintype "passive"))
      (node (ref "U$18") (pin "G") (pinfunction "G_G") (pintype "bidirectional"))
    )
    (net (code "37") (name "Net-(R51-Pad2)") (class "Default")
      (node (ref "R51") (pin "2") (pinfunction "2_2") (pintype "passive"))
      (node (ref "U$6") (pin "MTDO/13") (pinfunction "MTDO/13_MTDO/13") (pintype "bidirectional"))
    )
    (net (code "38") (name "Net-(S1-O)") (class "Default")
      (node (ref "JP5") (pin "2") (pinfunction "2_2") (pintype "passive"))
      (node (ref "S1") (pin "1") (pinfunction "O_1") (pintype "passive"))
    )
    (net (code "39") (name "Net-(U$1-SIGNAL)") (class "Default")
      (node (ref "C6") (pin "1") (pinfunction "1_1") (pintype "passive"))
      (node (ref "L7") (pin "1") (pinfunction "1_1") (pintype "passive"))
      (node (ref "U$1") (pin "FEED") (pinfunction "SIGNAL_FEED") (pintype "bidirectional"))
    )
    (net (code "40") (name "Net-(U$2-SIGNAL)") (class "Default")
      (node (ref "C12") (pin "1") (pinfunction "1_1") (pintype "passive"))
      (node (ref "C13") (pin "2") (pinfunction "2_2") (pintype "passive"))
      (node (ref "U$2") (pin "FEED") (pinfunction "SIGNAL_FEED") (pintype "bidirectional"))
    )
    (net (code "41") (name "Net-(U$3-CLK)") (class "Default")
      (node (ref "R18") (pin "1") (pinfunction "1_1") (pintype "passive"))
      (node (ref "U$3") (pin "6") (pinfunction "CLK_6") (pintype "bidirectional"))
    )
    (net (code "42") (name "Net-(U$3-CS#)") (class "Default")
      (node (ref "U$3") (pin "1") (pinfunction "CS#_1") (pintype "bidirectional"))
      (node (ref "U$6") (pin "SD_CMD/20") (pinfunction "SD_CMD/20_SD_CMD/20") (pintype "bidirectional"))
    )
    (net (code "43") (name "Net-(U$3-DIO)") (class "Default")
      (node (ref "U$3") (pin "5") (pinfunction "DIO_5") (pintype "bidirectional"))
      (node (ref "U$6") (pin "SD_DATA_1/23") (pinfunction "SD_DATA_1/23_SD_DATA_1/23") (pintype "bidirectional"))
    )
    (net (code "44") (name "Net-(U$3-DO)") (class "Default")
      (node (ref "U$3") (pin "2") (pinfunction "DO_2") (pintype "bidirectional"))
      (node (ref "U$6") (pin "SD_DATA_0/22") (pinfunction "SD_DATA_0/22_SD_DATA_0/22") (pintype "bidirectional"))
    )
    (net (code "45") (name "Net-(U$3-HOLD#)") (class "Default")
      (node (ref "U$3") (pin "7") (pinfunction "HOLD#_7") (pintype "bidirectional"))
      (node (ref "U$6") (pin "SD_DATA_2/18") (pinfunction "SD_DATA_2/18_SD_DATA_2/18") (pintype "bidirectional"))
    )
    (net (code "46") (name "Net-(U$3-WP#)") (class "Default")
      (node (ref "U$3") (pin "3") (pinfunction "WP#_3") (pintype "bidirectional"))
      (node (ref "U$6") (pin "SD_DATA_3/19") (pinfunction "SD_DATA_3/19_SD_DATA_3/19") (pintype "bidirectional"))
    )
    (net (code "47") (name "Net-(U$4-ANT1{slash}12)") (class "Default")
      (node (ref "L2") (pin "1") (pinfunction "1_1") (pintype "passive"))
      (node (ref "L5") (pin "2") (pinfunction "2_2") (pintype "passive"))
      (node (ref "U$4") (pin "12") (pinfunction "ANT1/12_12") (pintype "bidirectional"))
    )
    (net (code "48") (name "Net-(U$4-ANT2{slash}13)") (class "Default")
      (node (ref "L5") (pin "1") (pinfunction "1_1") (pintype "passive"))
      (node (ref "L6") (pin "1") (pinfunction "1_1") (pintype "passive"))
      (node (ref "U$4") (pin "13") (pinfunction "ANT2/13_13") (pintype "bidirectional"))
    )
    (net (code "49") (name "Net-(U$4-DVDD{slash}19)") (class "Default")
      (node (ref "C8") (pin "2") (pinfunction "2_2") (pintype "passive"))
      (node (ref "U$4") (pin "19") (pinfunction "DVDD/19_19") (pintype "bidirectional"))
    )
    (net (code "50") (name "Net-(U$4-IREF{slash}16)") (class "Default")
      (node (ref "R12") (pin "1") (pinfunction "1_1") (pintype "passive"))
      (node (ref "U$4") (pin "16") (pinfunction "IREF/16_16") (pintype "bidirectional"))
    )
    (net (code "51") (name "Net-(U$4-VDD_PA{slash}11)") (class "Default")
      (node (ref "C10") (pin "1") (pinfunction "1_1") (pintype "passive"))
      (node (ref "C9") (pin "1") (pinfunction "1_1") (pintype "passive"))
      (node (ref "L2") (pin "2") (pinfunction "2_2") (pintype "passive"))
      (node (ref "U$4") (pin "11") (pinfunction "VDD_PA/11_11") (pintype "bidirectional"))
    )
    (net (code "52") (name "Net-(U$4-XC1{slash}10)") (class "Default")
      (node (ref "C15") (pin "1") (pinfunction "1_1") (pintype "passive"))
      (node (ref "R11") (pin "2") (pinfunction "2_2") (pintype "passive"))
      (node (ref "U$4") (pin "10") (pinfunction "XC1/10_10") (pintype "bidirectional"))
      (node (ref "Y4") (pin "3") (pinfunction "2_3") (pintype "passive"))
    )
    (net (code "53") (name "Net-(U$4-XC2{slash}9)") (class "Default")
      (node (ref "C14") (pin "1") (pinfunction "1_1") (pintype "passive"))
      (node (ref "R11") (pin "1") (pinfunction "1_1") (pintype "passive"))
      (node (ref "U$4") (pin "9") (pinfunction "XC2/9_9") (pintype "bidirectional"))
      (node (ref "Y4") (pin "1") (pinfunction "1_1") (pintype "passive"))
    )
    (net (code "54") (name "Net-(U$7-NC{slash}TDI)") (class "Default")
      (node (ref "R52") (pin "2") (pinfunction "2_2") (pintype "passive"))
      (node (ref "U$7") (pin "8") (pinfunction "NC/TDI_8") (pintype "bidirectional"))
      (node (ref "U1") (pin "23") (pinfunction "PTA1_23") (pintype "bidirectional"))
    )
    (net (code "55") (name "Net-(U$7-SWO{slash}TDO)") (class "Default")
      (node (ref "U$7") (pin "6") (pinfunction "SWO/TDO_6") (pintype "bidirectional"))
      (node (ref "U1") (pin "24") (pinfunction "PTA2_24") (pintype "bidirectional"))
    )
    (net (code "56") (name "Net-(U$7-~{RESET})") (class "Default")
      (node (ref "R53") (pin "2") (pinfunction "2_2") (pintype "passive"))
      (node (ref "U$7") (pin "10") (pinfunction "~{RESET}_10") (pintype "bidirectional"))
      (node (ref "U1") (pin "34") (pinfunction "RESET_B_34") (pintype "bidirectional"))
    )
    (net (code "57") (name "Net-(U$20-A0)") (class "Default")
      (node (ref "R21") (pin "1") (pinfunction "1_1") (pintype "passive"))
      (node (ref "U$20") (pin "22") (pinfunction "A0_22") (pintype "bidirectional"))
    )
    (net (code "58") (name "Net-(U$20-A1)") (class "Default")
      (node (ref "R20") (pin "1") (pinfunction "1_1") (pintype "passive"))
      (node (ref "U$20") (pin "23") (pinfunction "A1_23") (pintype "bidirectional"))
    )
    (net (code "59") (name "Net-(U$20-A2)") (class "Default")
      (node (ref "R19") (pin "1") (pinfunction "1_1") (pintype "passive"))
      (node (ref "U$20") (pin "24") (pinfunction "A2_24") (pintype "bidirectional"))
    )
    (net (code "60") (name "Net-(U$20-LED0)") (class "Default")
      (node (ref "R26") (pin "1") (pinfunction "1_1") (pintype "passive"))
      (node (ref "U$20") (pin "1") (pinfunction "LED0_1") (pintype "bidirectional"))
    )
    (net (code "61") (name "Net-(U$20-LED1)") (class "Default")
      (node (ref "R25") (pin "1") (pinfunction "1_1") (pintype "passive"))
      (node (ref "U$20") (pin "2") (pinfunction "LED1_2") (pintype "bidirectional"))
    )
    (net (code "62") (name "Net-(U$20-LED2)") (class "Default")
      (node (ref "R27") (pin "1") (pinfunction "1_1") (pintype "passive"))
      (node (ref "U$20") (pin "3") (pinfunction "LED2_3") (pintype "bidirectional"))
    )
    (net (code "63") (name "Net-(U$20-LED3)") (class "Default")
      (node (ref "R29") (pin "1") (pinfunction "1_1") (pintype "passive"))
      (node (ref "U$20") (pin "4") (pinfunction "LED3_4") (pintype "bidirectional"))
    )
    (net (code "64") (name "Net-(U$20-LED4)") (class "Default")
      (node (ref "R30") (pin "1") (pinfunction "1_1") (pintype "passive"))
      (node (ref "U$20") (pin "5") (pinfunction "LED4_5") (pintype "bidirectional"))
    )
    (net (code "65") (name "Net-(U$20-LED5)") (class "Default")
      (node (ref "R28") (pin "1") (pinfunction "1_1") (pintype "passive"))
      (node (ref "U$20") (pin "6") (pinfunction "LED5_6") (pintype "bidirectional"))
    )
    (net (code "66") (name "Net-(U$20-LED6)") (class "Default")
      (node (ref "R32") (pin "1") (pinfunction "1_1") (pintype "passive"))
      (node (ref "U$20") (pin "7") (pinfunction "LED6_7") (pintype "bidirectional"))
    )
    (net (code "67") (name "Net-(U$20-LED7)") (class "Default")
      (node (ref "R33") (pin "1") (pinfunction "1_1") (pintype "passive"))
      (node (ref "U$20") (pin "8") (pinfunction "LED7_8") (pintype "bidirectional"))
    )
    (net (code "68") (name "Net-(U$20-LED8)") (class "Default")
      (node (ref "R31") (pin "1") (pinfunction "1_1") (pintype "passive"))
      (node (ref "U$20") (pin "10") (pinfunction "LED8_10") (pintype "bidirectional"))
    )
    (net (code "69") (name "Net-(U$20-LED9)") (class "Default")
      (node (ref "R35") (pin "1") (pinfunction "1_1") (pintype "passive"))
      (node (ref "U$20") (pin "11") (pinfunction "LED9_11") (pintype "bidirectional"))
    )
    (net (code "70") (name "Net-(U$20-LED10)") (class "Default")
      (node (ref "R36") (pin "1") (pinfunction "1_1") (pintype "passive"))
      (node (ref "U$20") (pin "12") (pinfunction "LED10_12") (pintype "bidirectional"))
    )
    (net (code "71") (name "Net-(U$20-LED11)") (class "Default")
      (node (ref "R34") (pin "1") (pinfunction "1_1") (pintype "passive"))
      (node (ref "U$20") (pin "13") (pinfunction "LED11_13") (pintype "bidirectional"))
    )
    (net (code "72") (name "Net-(U$20-LED12)") (class "Default")
      (node (ref "JP3") (pin "4") (pinfunction "4_4") (pintype "passive"))
      (node (ref "U$20") (pin "14") (pinfunction "LED12_14") (pintype "bidirectional"))
    )
    (net (code "73") (name "Net-(U$20-LED13)") (class "Default")
      (node (ref "JP3") (pin "3") (pinfunction "3_3") (pintype "passive"))
      (node (ref "U$20") (pin "15") (pinfunction "LED13_15") (pintype "bidirectional"))
    )
    (net (code "74") (name "Net-(U$20-LED14)") (class "Default")
      (node (ref "JP3") (pin "2") (pinfunction "2_2") (pintype "passive"))
      (node (ref "U$20") (pin "16") (pinfunction "LED14_16") (pintype "bidirectional"))
    )
    (net (code "75") (name "Net-(U$20-LED15)") (class "Default")
      (node (ref "JP3") (pin "1") (pinfunction "1_1") (pintype "passive"))
      (node (ref "U$20") (pin "17") (pinfunction "LED15_17") (pintype "bidirectional"))
    )
    (net (code "76") (name "Net-(U$21-A0)") (class "Default")
      (node (ref "R22") (pin "1") (pinfunction "1_1") (pintype "passive"))
      (node (ref "U$21") (pin "22") (pinfunction "A0_22") (pintype "bidirectional"))
    )
    (net (code "77") (name "Net-(U$21-A1)") (class "Default")
      (node (ref "R23") (pin "1") (pinfunction "1_1") (pintype "passive"))
      (node (ref "U$21") (pin "23") (pinfunction "A1_23") (pintype "bidirectional"))
    )
    (net (code "78") (name "Net-(U$21-A2)") (class "Default")
      (node (ref "R24") (pin "1") (pinfunction "1_1") (pintype "passive"))
      (node (ref "U$21") (pin "24") (pinfunction "A2_24") (pintype "bidirectional"))
    )
    (net (code "79") (name "Net-(U$21-LED0)") (class "Default")
      (node (ref "R38") (pin "1") (pinfunction "1_1") (pintype "passive"))
      (node (ref "U$21") (pin "1") (pinfunction "LED0_1") (pintype "bidirectional"))
    )
    (net (code "80") (name "Net-(U$21-LED1)") (class "Default")
      (node (ref "R39") (pin "1") (pinfunction "1_1") (pintype "passive"))
      (node (ref "U$21") (pin "2") (pinfunction "LED1_2") (pintype "bidirectional"))
    )
    (net (code "81") (name "Net-(U$21-LED2)") (class "Default")
      (node (ref "R37") (pin "1") (pinfunction "1_1") (pintype "passive"))
      (node (ref "U$21") (pin "3") (pinfunction "LED2_3") (pintype "bidirectional"))
    )
    (net (code "82") (name "Net-(U$21-LED3)") (class "Default")
      (node (ref "R41") (pin "1") (pinfunction "1_1") (pintype "passive"))
      (node (ref "U$21") (pin "4") (pinfunction "LED3_4") (pintype "bidirectional"))
    )
    (net (code "83") (name "Net-(U$21-LED4)") (class "Default")
      (node (ref "R42") (pin "1") (pinfunction "1_1") (pintype "passive"))
      (node (ref "U$21") (pin "5") (pinfunction "LED4_5") (pintype "bidirectional"))
    )
    (net (code "84") (name "Net-(U$21-LED5)") (class "Default")
      (node (ref "R40") (pin "1") (pinfunction "1_1") (pintype "passive"))
      (node (ref "U$21") (pin "6") (pinfunction "LED5_6") (pintype "bidirectional"))
    )
    (net (code "85") (name "Net-(U$21-LED6)") (class "Default")
      (node (ref "R44") (pin "1") (pinfunction "1_1") (pintype "passive"))
      (node (ref "U$21") (pin "7") (pinfunction "LED6_7") (pintype "bidirectional"))
    )
    (net (code "86") (name "Net-(U$21-LED7)") (class "Default")
      (node (ref "R45") (pin "1") (pinfunction "1_1") (pintype "passive"))
      (node (ref "U$21") (pin "8") (pinfunction "LED7_8") (pintype "bidirectional"))
    )
    (net (code "87") (name "Net-(U$21-LED8)") (class "Default")
      (node (ref "R43") (pin "1") (pinfunction "1_1") (pintype "passive"))
      (node (ref "U$21") (pin "10") (pinfunction "LED8_10") (pintype "bidirectional"))
    )
    (net (code "88") (name "Net-(U$21-LED9)") (class "Default")
      (node (ref "R47") (pin "1") (pinfunction "1_1") (pintype "passive"))
      (node (ref "U$21") (pin "11") (pinfunction "LED9_11") (pintype "bidirectional"))
    )
    (net (code "89") (name "Net-(U$21-LED10)") (class "Default")
      (node (ref "R48") (pin "1") (pinfunction "1_1") (pintype "passive"))
      (node (ref "U$21") (pin "12") (pinfunction "LED10_12") (pintype "bidirectional"))
    )
    (net (code "90") (name "Net-(U$21-LED11)") (class "Default")
      (node (ref "R46") (pin "1") (pinfunction "1_1") (pintype "passive"))
      (node (ref "U$21") (pin "13") (pinfunction "LED11_13") (pintype "bidirectional"))
    )
    (net (code "91") (name "Net-(U1-EXTAL32)") (class "Default")
      (node (ref "C32") (pin "2") (pinfunction "2_2") (pintype "passive"))
      (node (ref "U1") (pin "20") (pinfunction "EXTAL32_20") (pintype "bidirectional"))
      (node (ref "Y1") (pin "P$1") (pinfunction "1_P$1") (pintype "passive"))
    )
    (net (code "92") (name "Net-(U1-PTA18)") (class "Default")
      (node (ref "C29") (pin "2") (pinfunction "2_2") (pintype "passive"))
      (node (ref "U1") (pin "32") (pinfunction "PTA18_32") (pintype "bidirectional"))
      (node (ref "Y2") (pin "3") (pinfunction "2_3") (pintype "passive"))
    )
    (net (code "93") (name "Net-(U1-PTA19)") (class "Default")
      (node (ref "C30") (pin "2") (pinfunction "2_2") (pintype "passive"))
      (node (ref "U1") (pin "33") (pinfunction "PTA19_33") (pintype "bidirectional"))
      (node (ref "Y2") (pin "1") (pinfunction "1_1") (pintype "passive"))
    )
    (net (code "94") (name "Net-(U1-PTD6)") (class "Default")
      (node (ref "R8") (pin "1") (pinfunction "1_1") (pintype "passive"))
      (node (ref "U1") (pin "63") (pinfunction "PTD6_63") (pintype "bidirectional"))
    )
    (net (code "95") (name "Net-(U1-PTD7)") (class "Default")
      (node (ref "R17") (pin "1") (pinfunction "1_1") (pintype "passive"))
      (node (ref "U1") (pin "64") (pinfunction "PTD7_64") (pintype "bidirectional"))
    )
    (net (code "96") (name "Net-(U1-VDDA)") (class "Default")
      (node (ref "C17") (pin "1") (pinfunction "1_1") (pintype "passive"))
      (node (ref "L3") (pin "1") (pinfunction "1_1") (pintype "passive"))
      (node (ref "R16") (pin "1") (pinfunction "1_1") (pintype "passive"))
      (node (ref "U1") (pin "13") (pinfunction "VDDA_13") (pintype "bidirectional"))
    )
    (net (code "97") (name "Net-(U1-VREFH)") (class "Default")
      (node (ref "C11") (pin "1") (pinfunction "1_1") (pintype "passive"))
      (node (ref "R16") (pin "2") (pinfunction "2_2") (pintype "passive"))
      (node (ref "U1") (pin "14") (pinfunction "VREFH_14") (pintype "bidirectional"))
    )
    (net (code "98") (name "Net-(U1-VREFL)") (class "Default")
      (node (ref "C11") (pin "2") (pinfunction "2_2") (pintype "passive"))
      (node (ref "C16") (pin "2") (pinfunction "2_2") (pintype "passive"))
      (node (ref "C17") (pin "2") (pinfunction "2_2") (pintype "passive"))
      (node (ref "L4") (pin "2") (pinfunction "2_2") (pintype "passive"))
      (node (ref "U1") (pin "15") (pinfunction "VREFL_15") (pintype "bidirectional"))
      (node (ref "U1") (pin "16") (pinfunction "VSSA_16") (pintype "bidirectional"))
    )
    (net (code "99") (name "Net-(U1-VREF_OUT)") (class "Default")
      (node (ref "C16") (pin "1") (pinfunction "1_1") (pintype "passive"))
      (node (ref "U1") (pin "17") (pinfunction "VREF_OUT_17") (pintype "bidirectional"))
    )
    (net (code "100") (name "Net-(U1-XTAL32)") (class "Default")
      (node (ref "C31") (pin "2") (pinfunction "2_2") (pintype "passive"))
      (node (ref "U1") (pin "19") (pinfunction "XTAL32_19") (pintype "bidirectional"))
      (node (ref "Y1") (pin "P$2") (pinfunction "2_P$2") (pintype "passive"))
    )
    (net (code "101") (name "Net-(U2-FB)") (class "Default")
      (node (ref "R6") (pin "2") (pinfunction "2_2") (pintype "passive"))
      (node (ref "R7") (pin "1") (pinfunction "1_1") (pintype "passive"))
      (node (ref "U2") (pin "10") (pinfunction "FB_10") (pintype "passive"))
    )
    (net (code "102") (name "Net-(U2-L)") (class "Default")
      (node (ref "L1") (pin "1") (pinfunction "1_1") (pintype "passive"))
      (node (ref "U2") (pin "3") (pinfunction "L_3") (pintype "passive"))
    )
    (net (code "103") (name "Net-(U2-UVLO)") (class "Default")
      (node (ref "C2") (pin "2") (pinfunction "2_2") (pintype "passive"))
      (node (ref "R3") (pin "1") (pinfunction "1_1") (pintype "passive"))
      (node (ref "R4") (pin "2") (pinfunction "2_2") (pintype "passive"))
      (node (ref "U2") (pin "7") (pinfunction "UVLO_7") (pintype "passive"))
    )
    (net (code "104") (name "Net-(U2-VAUX)") (class "Default")
      (node (ref "C4") (pin "1") (pinfunction "1_1") (pintype "passive"))
      (node (ref "U2") (pin "1") (pinfunction "VAUX_1") (pintype "passive"))
    )
    (net (code "105") (name "Net-(U3-REGOUT)") (class "Default")
      (node (ref "C27") (pin "2") (pinfunction "2_2") (pintype "passive"))
      (node (ref "U3") (pin "10") (pinfunction "REGOUT_10") (pintype "bidirectional"))
    )
    (net (code "106") (name "Net-(Y3-2)") (class "Default")
      (node (ref "C23") (pin "1") (pinfunction "1_1") (pintype "passive"))
      (node (ref "U$6") (pin "XTAL_IN/28") (pinfunction "XTAL_IN/28_XTAL_IN/28") (pintype "bidirectional"))
      (node (ref "Y3") (pin "3") (pinfunction "2_3") (pintype "passive"))
    )
    (net (code "107") (name "PS") (class "Default")
      (node (ref "R2") (pin "2") (pinfunction "2_2") (pintype "passive"))
      (node (ref "U2") (pin "8") (pinfunction "PS_8") (pintype "input"))
    )
    (net (code "108") (name "PTA0") (class "Default")
      (node (ref "R50") (pin "2") (pinfunction "2_2") (pintype "passive"))
      (node (ref "U$7") (pin "4") (pinfunction "SWDCLK/TCK_4") (pintype "bidirectional"))
      (node (ref "U1") (pin "22") (pinfunction "PTA0_22") (pintype "bidirectional"))
    )
    (net (code "109") (name "PTA3") (class "Default")
      (node (ref "R49") (pin "2") (pinfunction "2_2") (pintype "passive"))
      (node (ref "U$7") (pin "2") (pinfunction "SWDIO/TMS_2") (pintype "bidirectional"))
      (node (ref "U1") (pin "25") (pinfunction "PTA3_25") (pintype "bidirectional"))
    )
    (net (code "110") (name "PTB0") (class "Default")
      (node (ref "U1") (pin "35") (pinfunction "PTB0_35") (pintype "bidirectional"))
      (node (ref "U3") (pin "12") (pinfunction "INT_12") (pintype "bidirectional"))
    )
    (net (code "111") (name "PTB1") (class "Default")
      (node (ref "U1") (pin "36") (pinfunction "PTB1_36") (pintype "bidirectional"))
      (node (ref "U3") (pin "11") (pinfunction "FSYNC_11") (pintype "bidirectional"))
    )
    (net (code "112") (name "PTB16") (class "Default")
      (node (ref "U$6") (pin "U0TXD/26") (pinfunction "U0TXD/26_U0TXD/26") (pintype "bidirectional"))
      (node (ref "U1") (pin "39") (pinfunction "PTB16_39") (pintype "bidirectional"))
    )
    (net (code "113") (name "PTB17") (class "Default")
      (node (ref "U$6") (pin "U0RXD/25") (pinfunction "U0RXD/25_U0RXD/25") (pintype "bidirectional"))
      (node (ref "U1") (pin "40") (pinfunction "PTB17_40") (pintype "bidirectional"))
    )
    (net (code "114") (name "PTB18") (class "Default")
      (node (ref "U$6") (pin "GPIO0/15") (pinfunction "GPIO0/15_GPIO0/15") (pintype "bidirectional"))
      (node (ref "U1") (pin "41") (pinfunction "PTB18_41") (pintype "bidirectional"))
    )
    (net (code "115") (name "PTB19") (class "Default")
      (node (ref "U$6") (pin "GPIO2/14") (pinfunction "GPIO2/14_GPIO2/14") (pintype "bidirectional"))
      (node (ref "U1") (pin "42") (pinfunction "PTB19_42") (pintype "bidirectional"))
    )
    (net (code "116") (name "PTC0") (class "Default")
      (node (ref "R15") (pin "1") (pinfunction "1_1") (pintype "passive"))
      (node (ref "U$6") (pin "EXT_RSTB/32") (pinfunction "EXT_RSTB/32_EXT_RSTB/32") (pintype "bidirectional"))
      (node (ref "U1") (pin "43") (pinfunction "PTC0_43") (pintype "bidirectional"))
    )
    (net (code "117") (name "PTC1") (class "Default")
      (node (ref "U$6") (pin "CHIP_EN/7") (pinfunction "CHIP_EN/7_CHIP_EN/7") (pintype "bidirectional"))
      (node (ref "U1") (pin "44") (pinfunction "PTC1_44") (pintype "bidirectional"))
    )
    (net (code "118") (name "PTC3") (class "Default")
      (node (ref "U$6") (pin "XPD_DCDC/8") (pinfunction "XPD_DCDC/8_XPD_DCDC/8") (pintype "bidirectional"))
      (node (ref "U1") (pin "46") (pinfunction "PTC3_46") (pintype "bidirectional"))
    )
    (net (code "119") (name "PTC4") (class "Default")
      (node (ref "U$4") (pin "2") (pinfunction "CSN/2_2") (pintype "bidirectional"))
      (node (ref "U1") (pin "49") (pinfunction "PTC4_49") (pintype "bidirectional"))
    )
    (net (code "120") (name "PTC5") (class "Default")
      (node (ref "U$4") (pin "3") (pinfunction "SCK/3_3") (pintype "bidirectional"))
      (node (ref "U1") (pin "50") (pinfunction "PTC5_50") (pintype "bidirectional"))
    )
    (net (code "121") (name "PTC6") (class "Default")
      (node (ref "U$4") (pin "4") (pinfunction "MOSI/4_4") (pintype "bidirectional"))
      (node (ref "U1") (pin "51") (pinfunction "PTC6_51") (pintype "bidirectional"))
    )
    (net (code "122") (name "PTC7") (class "Default")
      (node (ref "U$4") (pin "5") (pinfunction "MISO/5_5") (pintype "bidirectional"))
      (node (ref "U1") (pin "52") (pinfunction "PTC7_52") (pintype "bidirectional"))
    )
    (net (code "123") (name "PTC8") (class "Default")
      (node (ref "U$4") (pin "6") (pinfunction "IRQ/6_6") (pintype "bidirectional"))
      (node (ref "U1") (pin "53") (pinfunction "PTC8_53") (pintype "bidirectional"))
    )
    (net (code "124") (name "PTC9") (class "Default")
      (node (ref "U$4") (pin "1") (pinfunction "CE/1_1") (pintype "bidirectional"))
      (node (ref "U1") (pin "54") (pinfunction "PTC9_54") (pintype "bidirectional"))
    )
    (net (code "125") (name "PTC10") (class "Default")
      (node (ref "JP1") (pin "12") (pinfunction "12_12") (pintype "passive"))
      (node (ref "U1") (pin "55") (pinfunction "PTC10_55") (pintype "bidirectional"))
    )
    (net (code "126") (name "PTC11") (class "Default")
      (node (ref "JP1") (pin "11") (pinfunction "11_11") (pintype "passive"))
      (node (ref "U1") (pin "56") (pinfunction "PTC11_56") (pintype "bidirectional"))
    )
    (net (code "127") (name "PTD0") (class "Default")
      (node (ref "JP1") (pin "10") (pinfunction "10_10") (pintype "passive"))
      (node (ref "U1") (pin "57") (pinfunction "PTD0_57") (pintype "bidirectional"))
    )
    (net (code "128") (name "PTD1") (class "Default")
      (node (ref "JP1") (pin "9") (pinfunction "9_9") (pintype "passive"))
      (node (ref "U1") (pin "58") (pinfunction "PTD1_58") (pintype "bidirectional"))
    )
    (net (code "129") (name "PTD2") (class "Default")
      (node (ref "JP1") (pin "8") (pinfunction "8_8") (pintype "passive"))
      (node (ref "U1") (pin "59") (pinfunction "PTD2_59") (pintype "bidirectional"))
    )
    (net (code "130") (name "PTD3") (class "Default")
      (node (ref "JP1") (pin "7") (pinfunction "7_7") (pintype "passive"))
      (node (ref "U1") (pin "60") (pinfunction "PTD3_60") (pintype "bidirectional"))
    )
    (net (code "131") (name "PTD4") (class "Default")
      (node (ref "JP1") (pin "6") (pinfunction "6_6") (pintype "passive"))
      (node (ref "U1") (pin "61") (pinfunction "PTD4_61") (pintype "bidirectional"))
    )
    (net (code "132") (name "PTD5") (class "Default")
      (node (ref "JP1") (pin "5") (pinfunction "5_5") (pintype "passive"))
      (node (ref "U1") (pin "62") (pinfunction "PTD5_62") (pintype "bidirectional"))
    )
    (net (code "133") (name "SCL") (class "Default")
      (node (ref "R14") (pin "2") (pinfunction "2_2") (pintype "passive"))
      (node (ref "U$20") (pin "19") (pinfunction "SCL_19") (pintype "bidirectional"))
      (node (ref "U$21") (pin "19") (pinfunction "SCL_19") (pintype "bidirectional"))
      (node (ref "U1") (pin "37") (pinfunction "PTB2_37") (pintype "bidirectional"))
      (node (ref "U3") (pin "23") (pinfunction "SCLK_23") (pintype "bidirectional"))
    )
    (net (code "134") (name "SDA") (class "Default")
      (node (ref "R13") (pin "2") (pinfunction "2_2") (pintype "passive"))
      (node (ref "U$20") (pin "20") (pinfunction "SDA_20") (pintype "bidirectional"))
      (node (ref "U$21") (pin "20") (pinfunction "SDA_20") (pintype "bidirectional"))
      (node (ref "U1") (pin "38") (pinfunction "PTB3_38") (pintype "bidirectional"))
      (node (ref "U3") (pin "24") (pinfunction "SDA/MOSI_24") (pintype "bidirectional"))
    )
    (net (code "135") (name "SOFTPOWER") (class "Default")
      (node (ref "R10") (pin "1") (pinfunction "1_1") (pintype "passive"))
      (node (ref "U2") (pin "6") (pinfunction "EN_6") (pintype "input"))
    )
    (net (code "136") (name "USB_D_N") (class "Default")
      (node (ref "U1") (pin "6") (pinfunction "USB0_DM_6") (pintype "bidirectional"))
    )
    (net (code "137") (name "USB_D_P") (class "Default")
      (node (ref "U1") (pin "5") (pinfunction "USB0_DP_5") (pintype "bidirectional"))
    )
    (net (code "138") (name "VCC") (class "Default")
      (node (ref "C1") (pin "1") (pinfunction "1_1") (pintype "passive"))
      (node (ref "C2") (pin "1") (pinfunction "1_1") (pintype "passive"))
      (node (ref "L1") (pin "2") (pinfunction "2_2") (pintype "passive"))
      (node (ref "R10") (pin "2") (pinfunction "2_2") (pintype "passive"))
      (node (ref "R2") (pin "1") (pinfunction "1_1") (pintype "passive"))
      (node (ref "R3") (pin "2") (pinfunction "2_2") (pintype "passive"))
      (node (ref "S1") (pin "2") (pinfunction "P_2") (pintype "passive"))
      (node (ref "U2") (pin "5") (pinfunction "VIN_5") (pintype "power_in"))
    )
    (net (code "139") (name "unconnected-(S1-S-Pad3)") (class "Default")
      (node (ref "S1") (pin "3") (pinfunction "S_3") (pintype "passive"))
    )
    (net (code "140") (name "unconnected-(U$6-PadDVDD{slash}24)") (class "Default")
      (node (ref "U$6") (pin "DVDD/24") (pinfunction "DVDD/24_DVDD/24") (pintype "bidirectional"))
    )
    (net (code "141") (name "unconnected-(U$6-PadMTDI{slash}10)") (class "Default")
      (node (ref "U$6") (pin "MTDI/10") (pinfunction "MTDI/10_MTDI/10") (pintype "bidirectional"))
    )
    (net (code "142") (name "unconnected-(U$6-PadMTMS{slash}9)") (class "Default")
      (node (ref "U$6") (pin "MTMS/9") (pinfunction "MTMS/9_MTMS/9") (pintype "bidirectional"))
    )
    (net (code "143") (name "unconnected-(U$6-PadTOUT{slash}6)") (class "Default")
      (node (ref "U$6") (pin "TOUT/6") (pinfunction "TOUT/6_TOUT/6") (pintype "bidirectional"))
    )
    (net (code "144") (name "unconnected-(U$6-PadVDD_RTC{slash}5)") (class "Default")
      (node (ref "U$6") (pin "VDD_RTC/5") (pinfunction "VDD_RTC/5_VDD_RTC/5") (pintype "bidirectional"))
    )
    (net (code "145") (name "unconnected-(U$6-PadVDD{slash}16)") (class "Default")
      (node (ref "U$6") (pin "VDD/16") (pinfunction "VDD/16_VDD/16") (pintype "bidirectional"))
    )
    (net (code "146") (name "unconnected-(U$20-LED16-Pad18)") (class "Default")
      (node (ref "U$20") (pin "18") (pinfunction "LED16_18") (pintype "bidirectional"))
    )
    (net (code "147") (name "unconnected-(U$21-LED12-Pad14)") (class "Default")
      (node (ref "U$21") (pin "14") (pinfunction "LED12_14") (pintype "bidirectional"))
    )
    (net (code "148") (name "unconnected-(U$21-LED13-Pad15)") (class "Default")
      (node (ref "U$21") (pin "15") (pinfunction "LED13_15") (pintype "bidirectional"))
    )
    (net (code "149") (name "unconnected-(U$21-LED14-Pad16)") (class "Default")
      (node (ref "U$21") (pin "16") (pinfunction "LED14_16") (pintype "bidirectional"))
    )
    (net (code "150") (name "unconnected-(U$21-LED15-Pad17)") (class "Default")
      (node (ref "U$21") (pin "17") (pinfunction "LED15_17") (pintype "bidirectional"))
    )
    (net (code "151") (name "unconnected-(U$21-LED16-Pad18)") (class "Default")
      (node (ref "U$21") (pin "18") (pinfunction "LED16_18") (pintype "bidirectional"))
    )
    (net (code "152") (name "unconnected-(U1-ADC0_DM0-Pad10)") (class "Default")
      (node (ref "U1") (pin "10") (pinfunction "ADC0_DM0_10") (pintype "bidirectional"))
    )
    (net (code "153") (name "unconnected-(U1-ADC0_DM3-Pad12)") (class "Default")
      (node (ref "U1") (pin "12") (pinfunction "ADC0_DM3_12") (pintype "bidirectional"))
    )
    (net (code "154") (name "unconnected-(U1-ADC0_DP0-Pad9)") (class "Default")
      (node (ref "U1") (pin "9") (pinfunction "ADC0_DP0_9") (pintype "bidirectional"))
    )
    (net (code "155") (name "unconnected-(U1-ADC0_DP3-Pad11)") (class "Default")
      (node (ref "U1") (pin "11") (pinfunction "ADC0_DP3_11") (pintype "bidirectional"))
    )
    (net (code "156") (name "unconnected-(U1-DAC0-Pad18)") (class "Default")
      (node (ref "U1") (pin "18") (pinfunction "DAC0_18") (pintype "bidirectional"))
    )
    (net (code "157") (name "unconnected-(U1-PTA4-Pad26)") (class "Default")
      (node (ref "U1") (pin "26") (pinfunction "PTA4_26") (pintype "bidirectional"))
    )
    (net (code "158") (name "unconnected-(U1-PTA5-Pad27)") (class "Default")
      (node (ref "U1") (pin "27") (pinfunction "PTA5_27") (pintype "bidirectional"))
    )
    (net (code "159") (name "unconnected-(U1-PTA12-Pad28)") (class "Default")
      (node (ref "U1") (pin "28") (pinfunction "PTA12_28") (pintype "bidirectional"))
    )
    (net (code "160") (name "unconnected-(U1-PTA13-Pad29)") (class "Default")
      (node (ref "U1") (pin "29") (pinfunction "PTA13_29") (pintype "bidirectional"))
    )
    (net (code "161") (name "unconnected-(U1-PTE0-Pad1)") (class "Default")
      (node (ref "U1") (pin "1") (pinfunction "PTE0_1") (pintype "bidirectional"))
    )
    (net (code "162") (name "unconnected-(U1-PTE1-Pad2)") (class "Default")
      (node (ref "U1") (pin "2") (pinfunction "PTE1_2") (pintype "bidirectional"))
    )
    (net (code "163") (name "unconnected-(U3-AUX_CL-Pad7)") (class "Default")
      (node (ref "U3") (pin "7") (pinfunction "AUX_CL_7") (pintype "bidirectional"))
    )
    (net (code "164") (name "unconnected-(U3-AUX_DA-Pad21)") (class "Default")
      (node (ref "U3") (pin "21") (pinfunction "AUX_DA_21") (pintype "bidirectional"))
    )
  )
)
